# EEZ_CF-DIC_r4B4.net
KiCad netlist of a schematic drawn in EAGLE
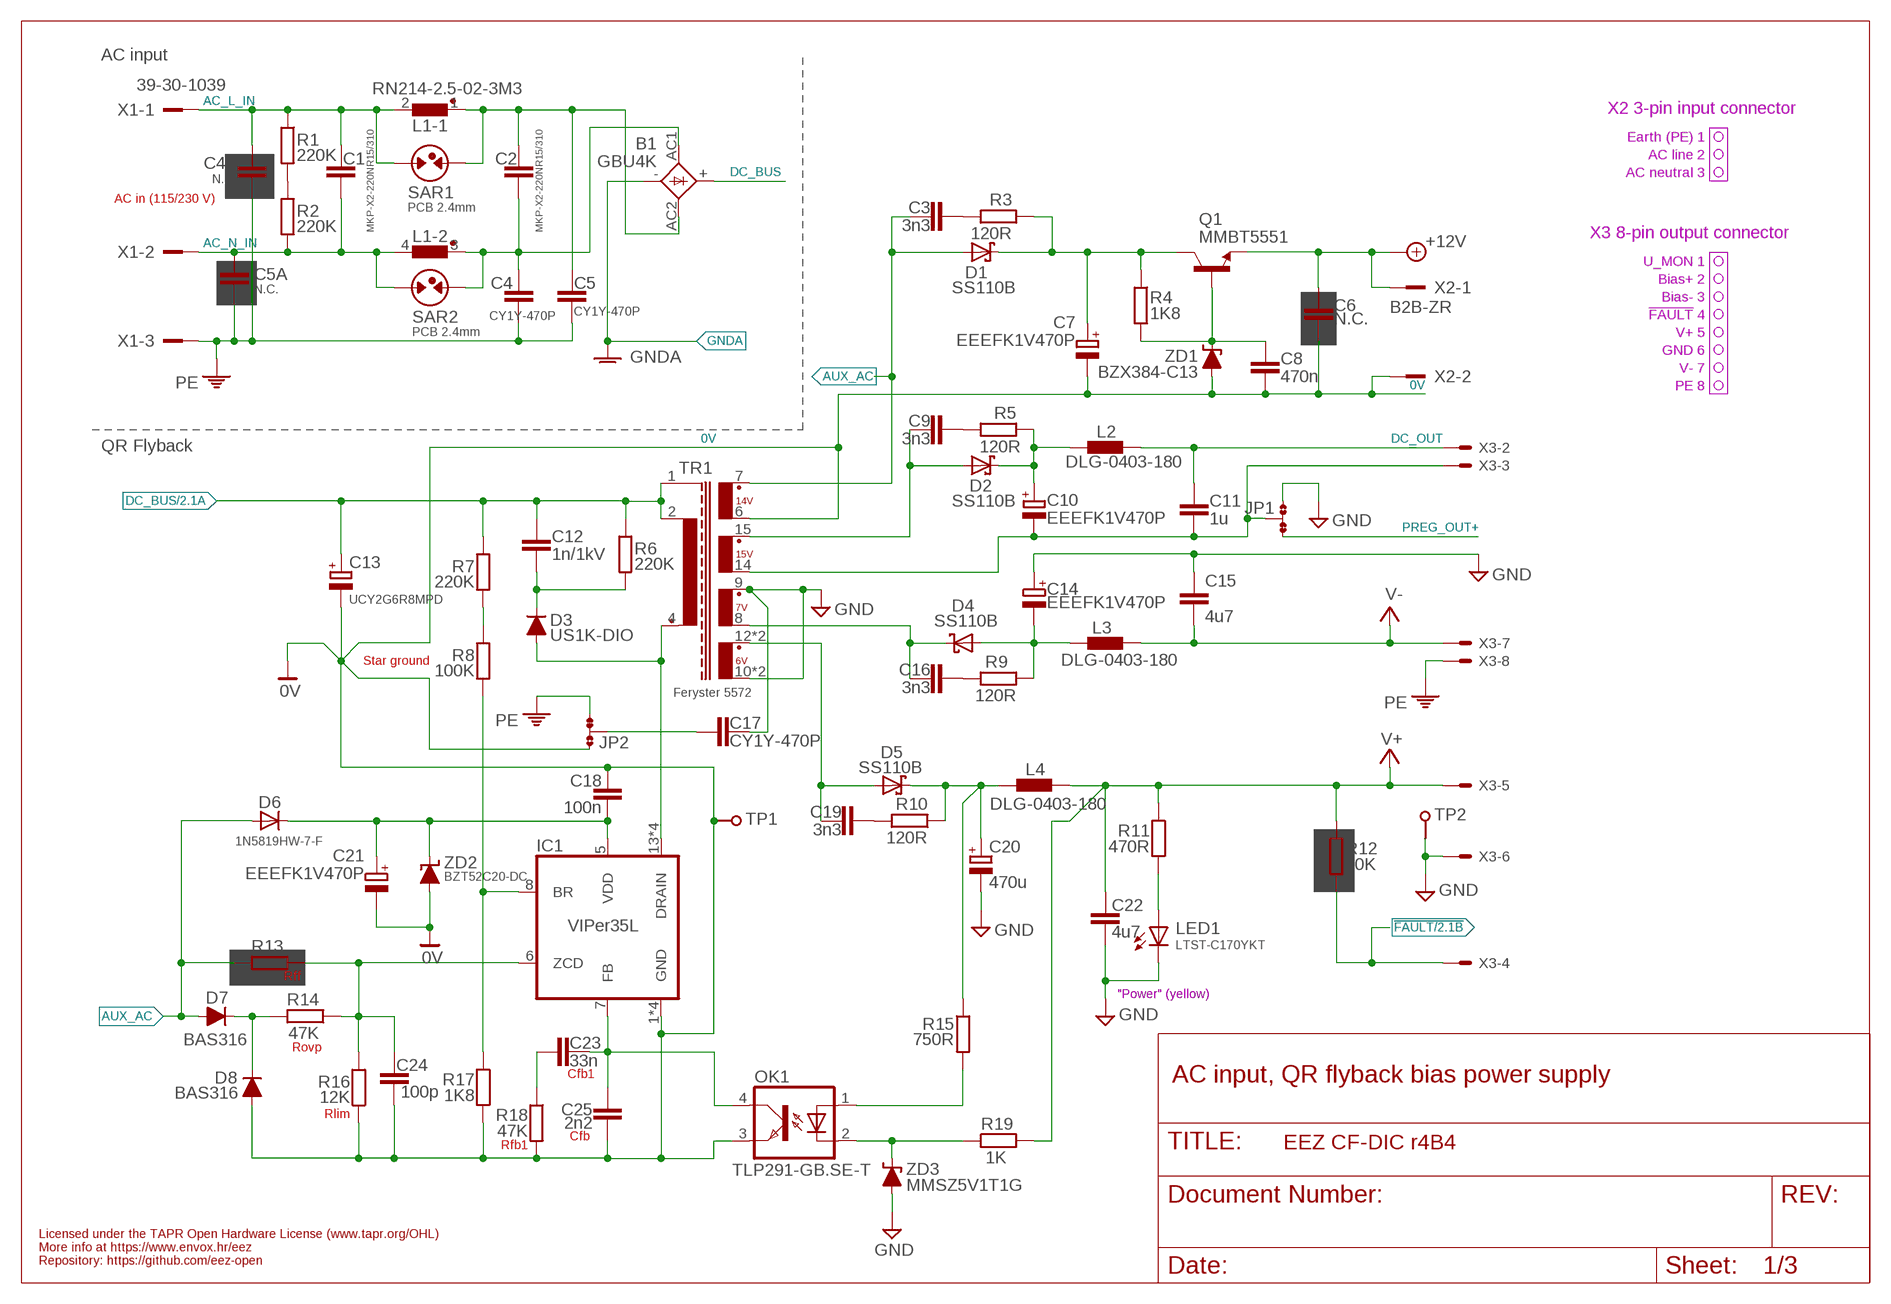
[diagram p0: schematic, sheet 1]
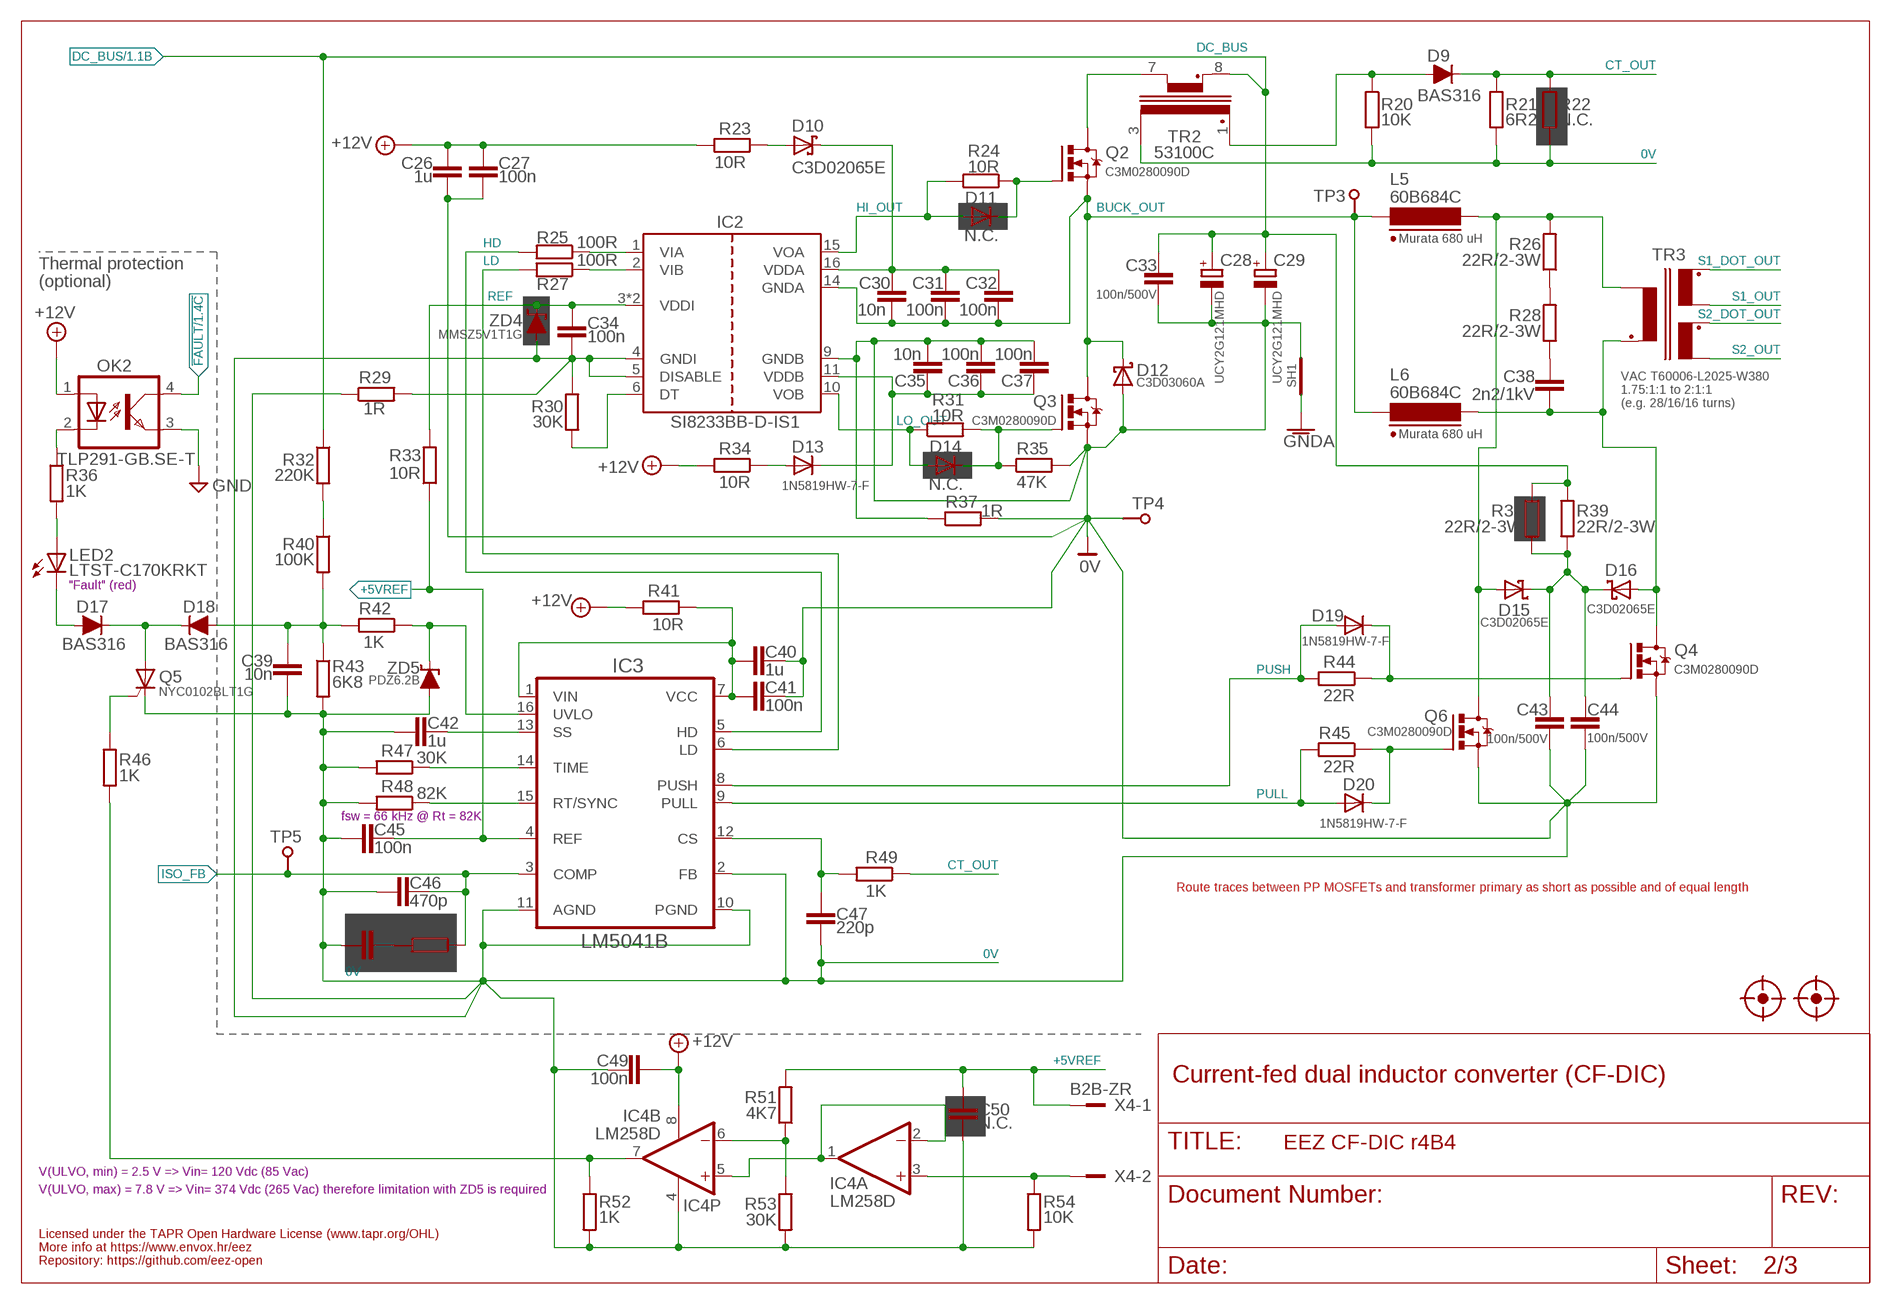
[diagram p1: schematic, sheet 2]
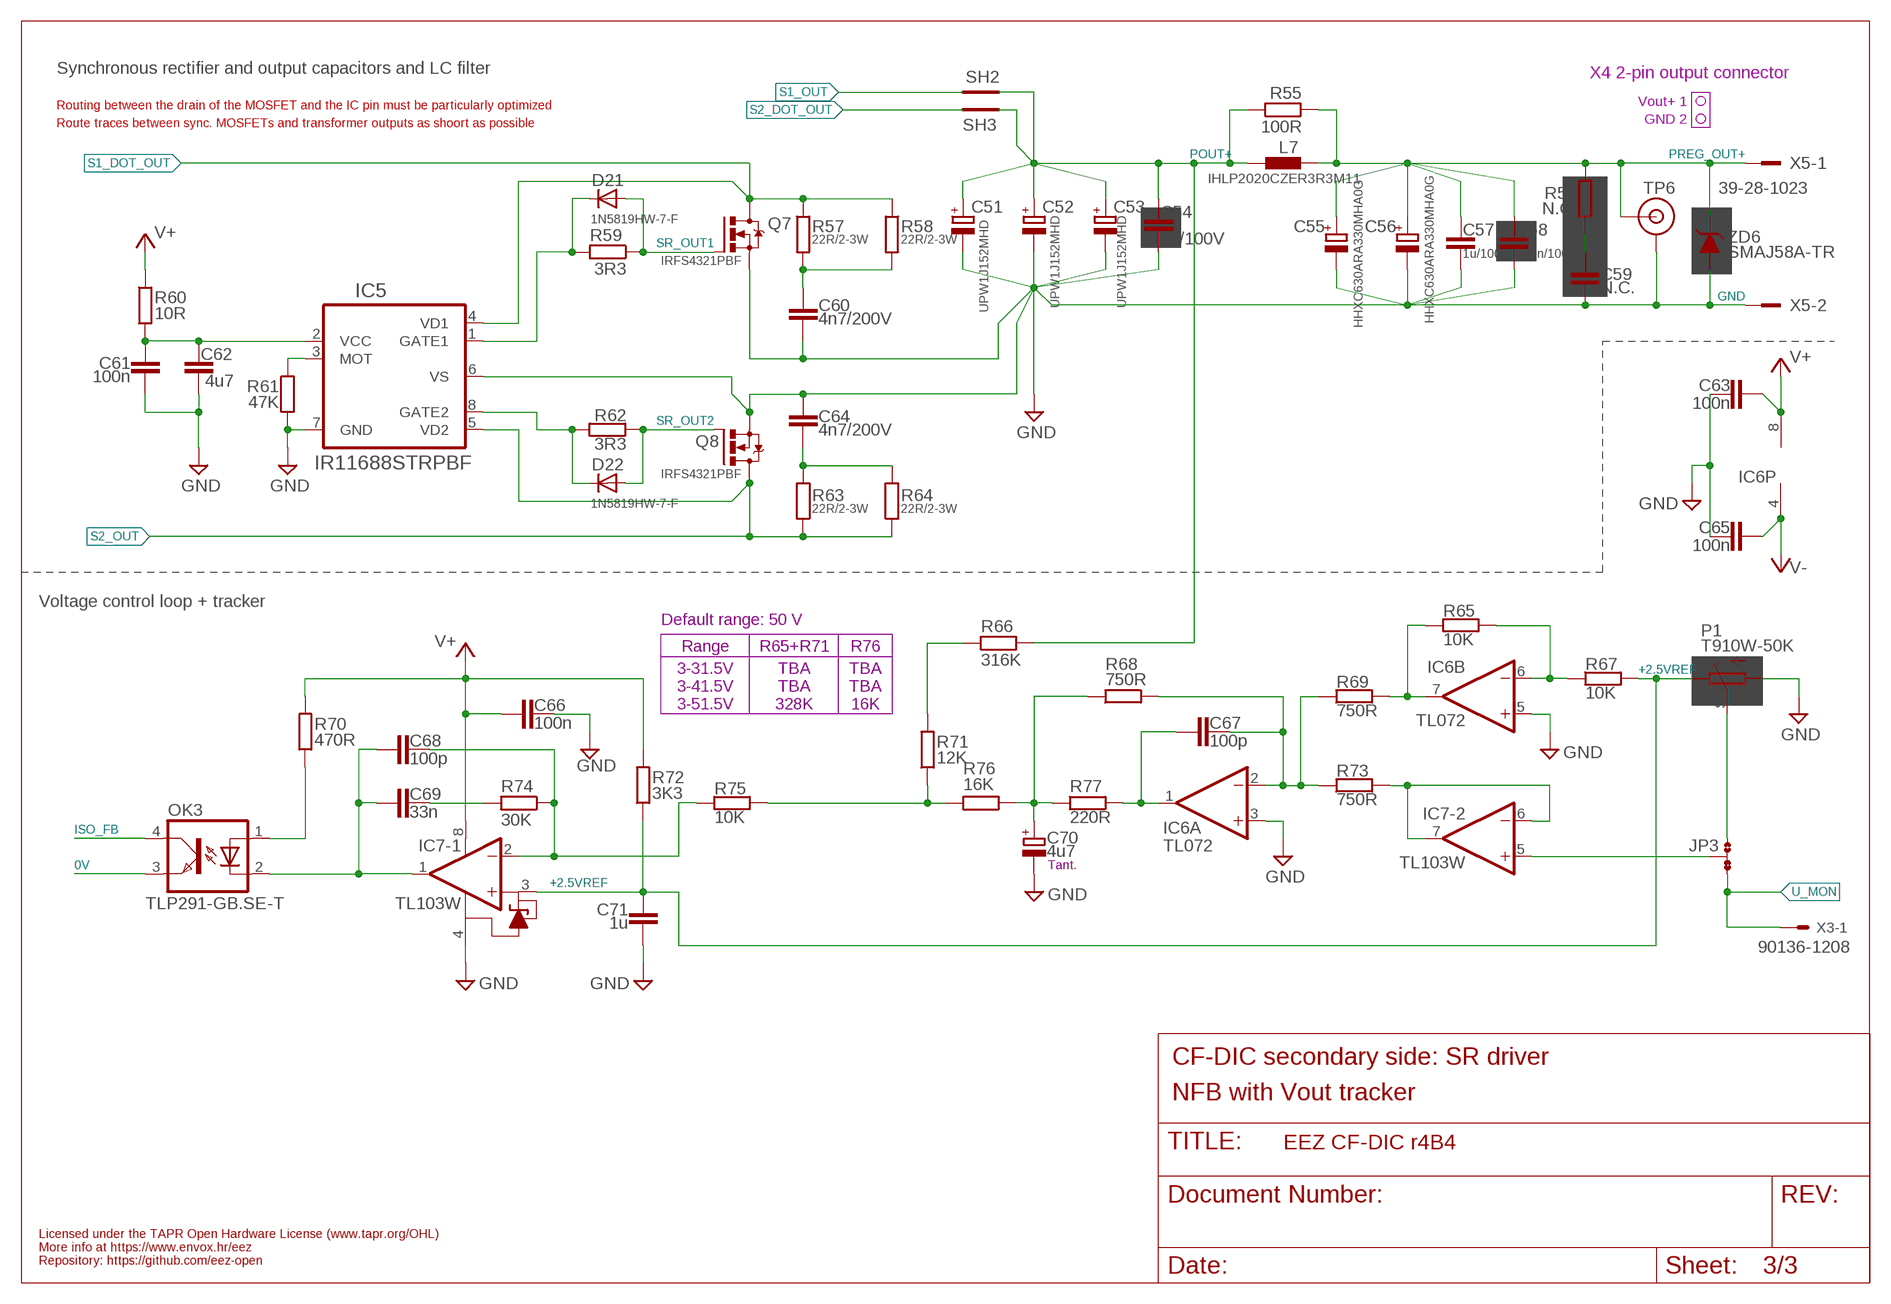
[diagram p2: schematic, sheet 3]

(export (version "E")
  (design (tool "Eeschema 10.0.6"))
  (components
    (comp (ref "C51")
      (value "UPW1J152MHD")
      (footprint "eagle-import:ECAP7.5_18")
      (libsource (lib "eagle-import") (part "ECAP7.5G_18MM"))
    )
    (comp (ref "C52")
      (value "UPW1J152MHD")
      (footprint "eagle-import:ECAP7.5_18")
      (libsource (lib "eagle-import") (part "ECAP7.5G_18MM"))
    )
    (comp (ref "C53")
      (value "UPW1J152MHD")
      (footprint "eagle-import:ECAP7.5_18")
      (libsource (lib "eagle-import") (part "ECAP7.5G_18MM"))
    )
    (comp (ref "C54")
      (value "1u/100V")
      (footprint "eagle-import:C1206")
      (libsource (lib "eagle-import") (part "C-EUC1206"))
    )
    (comp (ref "C55")
      (value "HHXC630ARA330MHA0G ")
      (footprint "eagle-import:CAPAE830X1050N")
      (fields
        (field (name "MPN") "EEE-FK1J470P")
        (field (name "TOLERANCE") "±20 %")
        (field (name "MPN_1") "EEE-FK1J470P")
        (field (name "OC_FARNELL") "9696032  ")
        (field (name "OC_NEWARK") "96K9403")
        (field (name "PACKAGE") "CASE-F")
        (field (name "SUPPLIER") "PANASONIC")
        (field (name "TOLERANCE_1") "±20 %")
        (field (name "VOLTAGERATING") "63 V")
      )
      (libsource (lib "eagle-import") (part "EEE--CASE-FFK1J470P"))
    )
    (comp (ref "C56")
      (value "HHXC630ARA330MHA0G")
      (footprint "eagle-import:CAPAE830X1050N")
      (fields (field (name "MPN") "EEE-FK1J470P") (field (name "TOLERANCE") "±20 %"))
      (libsource (lib "eagle-import") (part "EEE--CASE-FFK1J470P"))
    )
    (comp (ref "C57")
      (value "1u/100V")
      (footprint "eagle-import:C1206")
      (libsource (lib "eagle-import") (part "C-EUC1206"))
    )
    (comp (ref "C58")
      (value "100n/100V")
      (footprint "eagle-import:C0805")
      (libsource (lib "eagle-import") (part "C-EUC0805"))
    )
    (comp (ref "C59")
      (value "N.C.")
      (footprint "eagle-import:C1206")
      (libsource (lib "eagle-import") (part "C-EUC1206"))
    )
    (comp (ref "C60")
      (value "4n7/200V")
      (footprint "eagle-import:C1206")
      (libsource (lib "eagle-import") (part "C-EUC1206"))
    )
    (comp (ref "C61")
      (value "100n")
      (footprint "eagle-import:C0603")
      (libsource (lib "eagle-import") (part "C-EUC0603"))
    )
    (comp (ref "C62")
      (value "4u7")
      (footprint "eagle-import:C1206")
      (libsource (lib "eagle-import") (part "C-EUC1206"))
    )
    (comp (ref "C63")
      (value "100n")
      (footprint "eagle-import:C0603")
      (libsource (lib "eagle-import") (part "C-EUC0603"))
    )
    (comp (ref "C64")
      (value "4n7/200V")
      (footprint "eagle-import:C1206")
      (libsource (lib "eagle-import") (part "C-EUC1206"))
    )
    (comp (ref "C65")
      (value "100n")
      (footprint "eagle-import:C0603")
      (libsource (lib "eagle-import") (part "C-EUC0603"))
    )
    (comp (ref "C66")
      (value "100n")
      (footprint "eagle-import:C0603")
      (libsource (lib "eagle-import") (part "C-EUC0603"))
    )
    (comp (ref "C67")
      (value "100p")
      (footprint "eagle-import:C0805")
      (libsource (lib "eagle-import") (part "C-EUC0805"))
    )
    (comp (ref "C68")
      (value "100p")
      (footprint "eagle-import:C0805")
      (libsource (lib "eagle-import") (part "C-EUC0805"))
    )
    (comp (ref "C69")
      (value "33n")
      (footprint "eagle-import:C0805")
      (libsource (lib "eagle-import") (part "C-EUC0805"))
    )
    (comp (ref "C70")
      (value "4u7")
      (footprint "eagle-import:EC1206")
      (libsource (lib "eagle-import") (part "ECAP1206"))
    )
    (comp (ref "C71")
      (value "1u")
      (footprint "eagle-import:C0805")
      (libsource (lib "eagle-import") (part "C-EUC0805"))
    )
    (comp (ref "D21")
      (value "1N5819HW-7-F")
      (footprint "eagle-import:SOD323-W")
      (libsource (lib "eagle-import") (part "DIODE-SOD323-W"))
    )
    (comp (ref "D22")
      (value "1N5819HW-7-F")
      (footprint "eagle-import:SOD323-W")
      (libsource (lib "eagle-import") (part "DIODE-SOD323-W"))
    )
    (comp (ref "IC5")
      (value "IR11688STRPBF")
      (footprint "eagle-import:SO8")
      (libsource (lib "eagle-import") (part "IR11688"))
    )
    (comp (ref "IC6")
      (value "TL072")
      (footprint "eagle-import:SOIC127P600X173-8N")
      (libsource (lib "eagle-import") (part "TL072SOIC8"))
    )
    (comp (ref "IC7")
      (value "TL103W")
      (footprint "eagle-import:SOIC127P600X173-8N")
      (libsource (lib "eagle-import") (part "TL103W"))
    )
    (comp (ref "JP3")
      (value "JP3-CUT")
      (footprint "eagle-import:JP3-CUT")
      (libsource (lib "eagle-import") (part "JP3-CUT"))
    )
    (comp (ref "L7")
      (value "IHLP2020CZER3R3M11")
      (footprint "eagle-import:IHLP-2020BZ-11")
      (libsource (lib "eagle-import") (part "EEZ_inductors_and_transformers_IHLP-2020BZ-11"))
    )
    (comp (ref "OK3")
      (value "TLP291-GB.SE-T")
      (footprint "eagle-import:SO4")
      (libsource (lib "eagle-import") (part "TLP291"))
    )
    (comp (ref "P1")
      (value "T910W-50K")
      (footprint "eagle-import:S64W")
      (libsource (lib "eagle-import") (part "TPOT-S64W"))
    )
    (comp (ref "Q7")
      (value "IRFS4321PBF")
      (footprint "eagle-import:TO263")
      (libsource (lib "eagle-import") (part "N-MOSFETTO263"))
    )
    (comp (ref "Q8")
      (value "IRFS4321PBF")
      (footprint "eagle-import:TO263")
      (libsource (lib "eagle-import") (part "N-MOSFETTO263"))
    )
    (comp (ref "R55")
      (value "100R")
      (footprint "eagle-import:R0805")
      (libsource (lib "eagle-import") (part "R-EU_R0805"))
    )
    (comp (ref "R56")
      (value "N.C.")
      (footprint "eagle-import:R1210")
      (libsource (lib "eagle-import") (part "R-EU_R1210"))
    )
    (comp (ref "R57")
      (value "22R/2-3W")
      (footprint "eagle-import:R2512")
      (libsource (lib "eagle-import") (part "R-EU_R2512"))
    )
    (comp (ref "R58")
      (value "22R/2-3W")
      (footprint "eagle-import:R2512")
      (libsource (lib "eagle-import") (part "R-EU_R2512"))
    )
    (comp (ref "R59")
      (value "3R3")
      (footprint "eagle-import:R0805")
      (libsource (lib "eagle-import") (part "R-EU_R0805"))
    )
    (comp (ref "R60")
      (value "10R")
      (footprint "eagle-import:R0805")
      (libsource (lib "eagle-import") (part "R-EU_R0805"))
    )
    (comp (ref "R61")
      (value "47K")
      (footprint "eagle-import:R0805")
      (libsource (lib "eagle-import") (part "R-EU_R0805"))
    )
    (comp (ref "R62")
      (value "3R3")
      (footprint "eagle-import:R0805")
      (libsource (lib "eagle-import") (part "R-EU_R0805"))
    )
    (comp (ref "R63")
      (value "22R/2-3W")
      (footprint "eagle-import:R2512")
      (libsource (lib "eagle-import") (part "R-EU_R2512"))
    )
    (comp (ref "R64")
      (value "22R/2-3W")
      (footprint "eagle-import:R2512")
      (libsource (lib "eagle-import") (part "R-EU_R2512"))
    )
    (comp (ref "R65")
      (value "10K")
      (footprint "eagle-import:R0805")
      (libsource (lib "eagle-import") (part "R-EU_R0805"))
    )
    (comp (ref "R66")
      (value "316K")
      (footprint "eagle-import:R0805")
      (libsource (lib "eagle-import") (part "R-EU_R0805"))
    )
    (comp (ref "R67")
      (value "10K")
      (footprint "eagle-import:R0805")
      (libsource (lib "eagle-import") (part "R-EU_R0805"))
    )
    (comp (ref "R68")
      (value "750R")
      (footprint "eagle-import:R0805")
      (libsource (lib "eagle-import") (part "R-EU_R0805"))
    )
    (comp (ref "R69")
      (value "750R")
      (footprint "eagle-import:R0805")
      (libsource (lib "eagle-import") (part "R-EU_R0805"))
    )
    (comp (ref "R70")
      (value "470R")
      (footprint "eagle-import:R0805")
      (libsource (lib "eagle-import") (part "R-EU_R0805"))
    )
    (comp (ref "R71")
      (value "12K")
      (footprint "eagle-import:R0805")
      (libsource (lib "eagle-import") (part "R-EU_R0805"))
    )
    (comp (ref "R72")
      (value "3K3")
      (footprint "eagle-import:R0805")
      (libsource (lib "eagle-import") (part "R-EU_R0805"))
    )
    (comp (ref "R73")
      (value "750R")
      (footprint "eagle-import:R0805")
      (libsource (lib "eagle-import") (part "R-EU_R0805"))
    )
    (comp (ref "R74")
      (value "30K")
      (footprint "eagle-import:R0805")
      (libsource (lib "eagle-import") (part "R-EU_R0805"))
    )
    (comp (ref "R75")
      (value "10K")
      (footprint "eagle-import:R0805")
      (libsource (lib "eagle-import") (part "R-EU_R0805"))
    )
    (comp (ref "R76")
      (value "16K")
      (footprint "eagle-import:R0805")
      (libsource (lib "eagle-import") (part "R-EU_R0805"))
    )
    (comp (ref "R77")
      (value "220R")
      (footprint "eagle-import:R0805")
      (libsource (lib "eagle-import") (part "R-EU_R0805"))
    )
    (comp (ref "SH2")
      (value "SHORTNOHOLE")
      (footprint "eagle-import:SHORT_NOHOLE")
      (libsource (lib "eagle-import") (part "SHORTNOHOLE"))
    )
    (comp (ref "SH3")
      (value "SHORTNOHOLE")
      (footprint "eagle-import:SHORT_NOHOLE")
      (libsource (lib "eagle-import") (part "SHORTNOHOLE"))
    )
    (comp (ref "TP6")
      (value "TEST_POINT-2")
      (footprint "eagle-import:TP_1.1MM_2")
      (libsource (lib "eagle-import") (part "TEST_POINT-2"))
    )
    (comp (ref "X3")
      (value "90136-1208")
      (footprint "eagle-import:70543-08")
      (libsource (lib "eagle-import") (part "C-GRID-08-70543"))
    )
    (comp (ref "X5")
      (value "39-28-1023")
      (footprint "eagle-import:MINIFIT_5566-02A")
      (libsource (lib "eagle-import") (part "MINIFIT_5566-02A"))
    )
    (comp (ref "ZD6")
      (value "SMAJ58A-TR")
      (footprint "eagle-import:DO214AC")
      (libsource (lib "eagle-import") (part "PSMAXX"))
    )
    (comp (ref "B1")
      (value "GBU4K")
      (footprint "eagle-import:GBU4K_CRE")
      (libsource (lib "eagle-import") (part "BRIDGE-CREEPAGE"))
    )
    (comp (ref "C1")
      (value "MKP-X2-220NR15/310")
      (footprint "eagle-import:C150-072X183")
      (libsource (lib "eagle-import") (part "C-EU150-072X183"))
    )
    (comp (ref "C2")
      (value "MKP-X2-220NR15/310")
      (footprint "eagle-import:C150-072X183")
      (libsource (lib "eagle-import") (part "C-EU150-072X183"))
    )
    (comp (ref "C3")
      (value "3n3")
      (footprint "eagle-import:C0805")
      (libsource (lib "eagle-import") (part "C-EUC0805"))
    )
    (comp (ref "C4")
      (value "CY1Y-470P")
      (footprint "eagle-import:CY075-032X103")
      (libsource (lib "eagle-import") (part "C-EUCY"))
    )
    (comp (ref "C4A")
      (value "N.C.")
      (footprint "eagle-import:CY075-032X103")
      (libsource (lib "eagle-import") (part "C-EUCY"))
    )
    (comp (ref "C5")
      (value "CY1Y-470P")
      (footprint "eagle-import:CY075-032X103")
      (libsource (lib "eagle-import") (part "C-EUCY"))
    )
    (comp (ref "C5A")
      (value "N.C.")
      (footprint "eagle-import:CY075-032X103")
      (libsource (lib "eagle-import") (part "C-EUCY"))
    )
    (comp (ref "C6")
      (value "N.C.")
      (footprint "eagle-import:C0603")
      (libsource (lib "eagle-import") (part "C-EUC0603"))
    )
    (comp (ref "C7")
      (value "EEEFK1V470P")
      (footprint "eagle-import:CAPAE660X610N")
      (libsource (lib "eagle-import") (part "ECAPPANASONIC_H"))
    )
    (comp (ref "C8")
      (value "470n")
      (footprint "eagle-import:C0805")
      (libsource (lib "eagle-import") (part "C-EUC0805"))
    )
    (comp (ref "C9")
      (value "3n3")
      (footprint "eagle-import:C0805")
      (libsource (lib "eagle-import") (part "C-EUC0805"))
    )
    (comp (ref "C10")
      (value "EEEFK1V470P")
      (footprint "eagle-import:CAPAE660X610N")
      (libsource (lib "eagle-import") (part "ECAPPANASONIC_H"))
    )
    (comp (ref "C11")
      (value "1u")
      (footprint "eagle-import:C0805")
      (libsource (lib "eagle-import") (part "C-EUC0805"))
    )
    (comp (ref "C12")
      (value "1n/1kV")
      (footprint "eagle-import:C1210")
      (libsource (lib "eagle-import") (part "C-EUC1210"))
    )
    (comp (ref "C13")
      (value "UCY2G6R8MPD")
      (footprint "eagle-import:ECAP5_10.5")
      (libsource (lib "eagle-import") (part "ECAP5G_10.5MM"))
    )
    (comp (ref "C14")
      (value "EEEFK1V470P")
      (footprint "eagle-import:CAPAE660X610N")
      (libsource (lib "eagle-import") (part "ECAPPANASONIC_H"))
    )
    (comp (ref "C15")
      (value "4u7")
      (footprint "eagle-import:C1206")
      (libsource (lib "eagle-import") (part "C-EUC1206"))
    )
    (comp (ref "C16")
      (value "3n3")
      (footprint "eagle-import:C0805")
      (libsource (lib "eagle-import") (part "C-EUC0805"))
    )
    (comp (ref "C17")
      (value "CY1Y-470P")
      (footprint "eagle-import:CY075-032X103")
      (libsource (lib "eagle-import") (part "C-EUCY"))
    )
    (comp (ref "C18")
      (value "100n")
      (footprint "eagle-import:C0603")
      (libsource (lib "eagle-import") (part "C-EUC0603"))
    )
    (comp (ref "C19")
      (value "3n3")
      (footprint "eagle-import:C0805")
      (libsource (lib "eagle-import") (part "C-EUC0805"))
    )
    (comp (ref "C20")
      (value "470u")
      (footprint "eagle-import:ECAP5_10.5")
      (libsource (lib "eagle-import") (part "ECAP5G_10.5MM"))
    )
    (comp (ref "C21")
      (value "EEEFK1V470P")
      (footprint "eagle-import:CAPAE660X610N")
      (libsource (lib "eagle-import") (part "ECAPPANASONIC_H"))
    )
    (comp (ref "C22")
      (value "4u7")
      (footprint "eagle-import:C1206")
      (libsource (lib "eagle-import") (part "C-EUC1206"))
    )
    (comp (ref "C23")
      (value "33n")
      (footprint "eagle-import:C0805")
      (libsource (lib "eagle-import") (part "C-EUC0805"))
    )
    (comp (ref "C24")
      (value "100p")
      (footprint "eagle-import:C0805")
      (libsource (lib "eagle-import") (part "C-EUC0805"))
    )
    (comp (ref "C25")
      (value "2n2")
      (footprint "eagle-import:C0805")
      (libsource (lib "eagle-import") (part "C-EUC0805"))
    )
    (comp (ref "D1")
      (value "SS110B")
      (footprint "eagle-import:SMB")
      (libsource (lib "eagle-import") (part "SCHOTTKYSMB"))
    )
    (comp (ref "D2")
      (value "SS110B")
      (footprint "eagle-import:SMB")
      (libsource (lib "eagle-import") (part "SCHOTTKYSMB"))
    )
    (comp (ref "D3")
      (value "US1K-DIO")
      (footprint "eagle-import:DO214AA")
      (libsource (lib "eagle-import") (part "DIODEDO214AA"))
    )
    (comp (ref "D4")
      (value "SS110B")
      (footprint "eagle-import:SMB")
      (libsource (lib "eagle-import") (part "SCHOTTKYSMB"))
    )
    (comp (ref "D5")
      (value "SS110B")
      (footprint "eagle-import:SMB")
      (libsource (lib "eagle-import") (part "SCHOTTKYSMB"))
    )
    (comp (ref "D6")
      (value "1N5819HW-7-F")
      (footprint "eagle-import:SOD323-W")
      (libsource (lib "eagle-import") (part "DIODE-SOD323-W"))
    )
    (comp (ref "D7")
      (value "BAS316")
      (footprint "eagle-import:SOD323-R")
      (libsource (lib "eagle-import") (part "DIODESOD323R"))
    )
    (comp (ref "D8")
      (value "BAS316")
      (footprint "eagle-import:SOD323-R")
      (libsource (lib "eagle-import") (part "DIODESOD323R"))
    )
    (comp (ref "IC1")
      (value "VIPer35L")
      (footprint "eagle-import:SOIC-16")
      (libsource (lib "eagle-import") (part "VIPER35"))
    )
    (comp (ref "JP1")
      (value "JP3-CUT")
      (footprint "eagle-import:JP3-CUT")
      (libsource (lib "eagle-import") (part "JP3-CUT"))
    )
    (comp (ref "JP2")
      (value "JP3-CUT")
      (footprint "eagle-import:JP3-CUT")
      (libsource (lib "eagle-import") (part "JP3-CUT"))
    )
    (comp (ref "L1")
      (value "RN214-2.5-02-3M3")
      (footprint "eagle-import:RN214")
      (fields (field (name "FARNELL") "1191518"))
      (libsource (lib "eagle-import") (part "EEZ_inductors_and_transformers_RN214"))
    )
    (comp (ref "L2")
      (value "DLG-0403-180")
      (footprint "eagle-import:DE0403")
      (libsource (lib "eagle-import") (part "EEZ_inductors_and_transformers_DE0403"))
    )
    (comp (ref "L3")
      (value "DLG-0403-180")
      (footprint "eagle-import:DE0403")
      (libsource (lib "eagle-import") (part "EEZ_inductors_and_transformers_DE0403"))
    )
    (comp (ref "L4")
      (value "DLG-0403-180")
      (footprint "eagle-import:DE0403")
      (libsource (lib "eagle-import") (part "EEZ_inductors_and_transformers_DE0403"))
    )
    (comp (ref "LED1")
      (value "LTST-C170YKT")
      (footprint "eagle-import:LED_0805")
      (libsource (lib "eagle-import") (part "LED0805"))
    )
    (comp (ref "OK1")
      (value "TLP291-GB.SE-T")
      (footprint "eagle-import:SO4")
      (libsource (lib "eagle-import") (part "TLP291"))
    )
    (comp (ref "Q1")
      (value "MMBT5551")
      (footprint "eagle-import:SOT23-BEC")
      (libsource (lib "eagle-import") (part "-NPN-SOT23-BECMMBT5551LT1"))
    )
    (comp (ref "R1")
      (value "220K")
      (footprint "eagle-import:R1206")
      (libsource (lib "eagle-import") (part "R-EU_R1206"))
    )
    (comp (ref "R2")
      (value "220K")
      (footprint "eagle-import:R1206")
      (libsource (lib "eagle-import") (part "R-EU_R1206"))
    )
    (comp (ref "R3")
      (value "120R")
      (footprint "eagle-import:R0805")
      (libsource (lib "eagle-import") (part "R-EU_R0805"))
    )
    (comp (ref "R4")
      (value "1K8")
      (footprint "eagle-import:R0805")
      (libsource (lib "eagle-import") (part "R-EU_R0805"))
    )
    (comp (ref "R5")
      (value "120R")
      (footprint "eagle-import:R0805")
      (libsource (lib "eagle-import") (part "R-EU_R0805"))
    )
    (comp (ref "R6")
      (value "220K")
      (footprint "eagle-import:R1206")
      (libsource (lib "eagle-import") (part "R-EU_R1206"))
    )
    (comp (ref "R7")
      (value "220K")
      (footprint "eagle-import:R1206")
      (libsource (lib "eagle-import") (part "R-EU_R1206"))
    )
    (comp (ref "R8")
      (value "100K")
      (footprint "eagle-import:R0805")
      (libsource (lib "eagle-import") (part "R-EU_R0805"))
    )
    (comp (ref "R9")
      (value "120R")
      (footprint "eagle-import:R0805")
      (libsource (lib "eagle-import") (part "R-EU_R0805"))
    )
    (comp (ref "R10")
      (value "120R")
      (footprint "eagle-import:R0805")
      (libsource (lib "eagle-import") (part "R-EU_R0805"))
    )
    (comp (ref "R11")
      (value "470R")
      (footprint "eagle-import:R0805")
      (libsource (lib "eagle-import") (part "R-EU_R0805"))
    )
    (comp (ref "R12")
      (value "10K")
      (footprint "eagle-import:R0805")
      (libsource (lib "eagle-import") (part "R-EU_R0805"))
    )
    (comp (ref "R13")
      (value "N.C.")
      (footprint "eagle-import:R0805")
      (libsource (lib "eagle-import") (part "R-EU_R0805"))
    )
    (comp (ref "R14")
      (value "47K")
      (footprint "eagle-import:R0805")
      (libsource (lib "eagle-import") (part "R-EU_R0805"))
    )
    (comp (ref "R15")
      (value "750R")
      (footprint "eagle-import:R0805")
      (libsource (lib "eagle-import") (part "R-EU_R0805"))
    )
    (comp (ref "R16")
      (value "12K")
      (footprint "eagle-import:R0805")
      (libsource (lib "eagle-import") (part "R-EU_R0805"))
    )
    (comp (ref "R17")
      (value "1K8")
      (footprint "eagle-import:R0805")
      (libsource (lib "eagle-import") (part "R-EU_R0805"))
    )
    (comp (ref "R18")
      (value "47K")
      (footprint "eagle-import:R0805")
      (libsource (lib "eagle-import") (part "R-EU_R0805"))
    )
    (comp (ref "R19")
      (value "1K")
      (footprint "eagle-import:R0805")
      (libsource (lib "eagle-import") (part "R-EU_R0805"))
    )
    (comp (ref "SAR1")
      (value "PCB 2.4mm")
      (footprint "eagle-import:PCB-SAR_2.4MM")
      (libsource (lib "eagle-import") (part "SARPCB-2.4MM"))
    )
    (comp (ref "SAR2")
      (value "PCB 2.4mm")
      (footprint "eagle-import:PCB-SAR_2.4MM")
      (libsource (lib "eagle-import") (part "SARPCB-2.4MM"))
    )
    (comp (ref "TP1")
      (value "PCB_TEST_TABSHIELD")
      (footprint "eagle-import:PCB_SHIELD_TAB")
      (libsource (lib "eagle-import") (part "PCB_TEST_TABSHIELD"))
    )
    (comp (ref "TP2")
      (value "PCB_TEST_TABSHIELD")
      (footprint "eagle-import:PCB_SHIELD_TAB")
      (libsource (lib "eagle-import") (part "PCB_TEST_TABSHIELD"))
    )
    (comp (ref "TR1")
      (value "Feryster 5572")
      (footprint "eagle-import:FERYSTER_5572")
      (libsource (lib "eagle-import") (part "EEZ_inductors_and_transformers_FERYSTER_5572"))
    )
    (comp (ref "X1")
      (value "39-30-1039")
      (footprint "eagle-import:MINIFIT_39301039_CRE")
      (libsource (lib "eagle-import") (part "MINIFIT_39301039-CREEPAGE"))
    )
    (comp (ref "X2")
      (value "B2B-ZR")
      (footprint "eagle-import:B2B-ZR")
      (libsource (lib "eagle-import") (part "B2B-ZR"))
    )
    (comp (ref "ZD1")
      (value "BZX384-C13")
      (footprint "eagle-import:SOD323-W")
      (libsource (lib "eagle-import") (part "ZENER-DIODESOD323"))
    )
    (comp (ref "ZD2")
      (value "BZT52C20-DC")
      (footprint "eagle-import:SOD123")
      (libsource (lib "eagle-import") (part "ZENER-DIODESOD123"))
    )
    (comp (ref "ZD3")
      (value "MMSZ5V1T1G")
      (footprint "eagle-import:SOD323-W")
      (libsource (lib "eagle-import") (part "ZENER-DIODESOD323"))
    )
    (comp (ref "C26")
      (value "1u")
      (footprint "eagle-import:C0805")
      (libsource (lib "eagle-import") (part "C-EUC0805"))
    )
    (comp (ref "C27")
      (value "100n")
      (footprint "eagle-import:C0603")
      (libsource (lib "eagle-import") (part "C-EUC0603"))
    )
    (comp (ref "C28")
      (value "UCY2G121MHD")
      (footprint "eagle-import:ECAP7.5_18")
      (libsource (lib "eagle-import") (part "ECAP7.5G_18MM"))
    )
    (comp (ref "C29")
      (value "UCY2G121MHD")
      (footprint "eagle-import:ECAP7.5_18")
      (libsource (lib "eagle-import") (part "ECAP7.5G_18MM"))
    )
    (comp (ref "C30")
      (value "10n")
      (footprint "eagle-import:C0603")
      (libsource (lib "eagle-import") (part "C-EUC0603"))
    )
    (comp (ref "C31")
      (value "100n")
      (footprint "eagle-import:C0603")
      (libsource (lib "eagle-import") (part "C-EUC0603"))
    )
    (comp (ref "C32")
      (value "100n")
      (footprint "eagle-import:C0603")
      (libsource (lib "eagle-import") (part "C-EUC0603"))
    )
    (comp (ref "C33")
      (value "100n/500V")
      (footprint "eagle-import:C1812")
      (libsource (lib "eagle-import") (part "C-EUC1812"))
    )
    (comp (ref "C34")
      (value "100n")
      (footprint "eagle-import:C0603")
      (libsource (lib "eagle-import") (part "C-EUC0603"))
    )
    (comp (ref "C35")
      (value "10n")
      (footprint "eagle-import:C0603")
      (libsource (lib "eagle-import") (part "C-EUC0603"))
    )
    (comp (ref "C36")
      (value "100n")
      (footprint "eagle-import:C0603")
      (libsource (lib "eagle-import") (part "C-EUC0603"))
    )
    (comp (ref "C37")
      (value "100n")
      (footprint "eagle-import:C0603")
      (libsource (lib "eagle-import") (part "C-EUC0603"))
    )
    (comp (ref "C38")
      (value "2n2/1kV")
      (footprint "eagle-import:C1210")
      (libsource (lib "eagle-import") (part "C-EUC1210"))
    )
    (comp (ref "C39")
      (value "10n")
      (footprint "eagle-import:C0603")
      (libsource (lib "eagle-import") (part "C-EUC0603"))
    )
    (comp (ref "C40")
      (value "1u")
      (footprint "eagle-import:C0805")
      (libsource (lib "eagle-import") (part "C-EUC0805"))
    )
    (comp (ref "C41")
      (value "100n")
      (footprint "eagle-import:C0603")
      (libsource (lib "eagle-import") (part "C-EUC0603"))
    )
    (comp (ref "C42")
      (value "1u")
      (footprint "eagle-import:C0805")
      (libsource (lib "eagle-import") (part "C-EUC0805"))
    )
    (comp (ref "C43")
      (value "100n/500V")
      (footprint "eagle-import:C1812")
      (libsource (lib "eagle-import") (part "C-EUC1812"))
    )
    (comp (ref "C44")
      (value "100n/500V")
      (footprint "eagle-import:C1812")
      (libsource (lib "eagle-import") (part "C-EUC1812"))
    )
    (comp (ref "C45")
      (value "100n")
      (footprint "eagle-import:C0603")
      (libsource (lib "eagle-import") (part "C-EUC0603"))
    )
    (comp (ref "C46")
      (value "470p")
      (footprint "eagle-import:C0805")
      (libsource (lib "eagle-import") (part "C-EUC0805"))
    )
    (comp (ref "C47")
      (value "220p")
      (footprint "eagle-import:C0805")
      (libsource (lib "eagle-import") (part "C-EUC0805"))
    )
    (comp (ref "C48")
      (value "N.C.")
      (footprint "eagle-import:C0805")
      (libsource (lib "eagle-import") (part "C-EUC0805"))
    )
    (comp (ref "C49")
      (value "100n")
      (footprint "eagle-import:C0603")
      (libsource (lib "eagle-import") (part "C-EUC0603"))
    )
    (comp (ref "C50")
      (value "N.C.")
      (footprint "eagle-import:C0603")
      (libsource (lib "eagle-import") (part "C-EUC0603"))
    )
    (comp (ref "D9")
      (value "BAS316")
      (footprint "eagle-import:SOD323-R")
      (libsource (lib "eagle-import") (part "DIODESOD323R"))
    )
    (comp (ref "D10")
      (value "C3D02065E")
      (footprint "eagle-import:TO252")
      (libsource (lib "eagle-import") (part "SCHOTTKY-SIC"))
    )
    (comp (ref "D11")
      (value "N.C.")
      (footprint "eagle-import:SOD323-W")
      (libsource (lib "eagle-import") (part "DIODE-SOD323-W"))
    )
    (comp (ref "D12")
      (value "C3D03060A")
      (footprint "eagle-import:TO220-2")
      (libsource (lib "eagle-import") (part "SCHOTTKY-TO220"))
    )
    (comp (ref "D13")
      (value "1N5819HW-7-F")
      (footprint "eagle-import:SOD323-W")
      (libsource (lib "eagle-import") (part "DIODE-SOD323-W"))
    )
    (comp (ref "D14")
      (value "N.C.")
      (footprint "eagle-import:SOD323-W")
      (libsource (lib "eagle-import") (part "DIODE-SOD323-W"))
    )
    (comp (ref "D15")
      (value "C3D02065E")
      (footprint "eagle-import:TO252")
      (libsource (lib "eagle-import") (part "SCHOTTKY-SIC"))
    )
    (comp (ref "D16")
      (value "C3D02065E")
      (footprint "eagle-import:TO252")
      (libsource (lib "eagle-import") (part "SCHOTTKY-SIC"))
    )
    (comp (ref "D17")
      (value "BAS316")
      (footprint "eagle-import:SOD323-R")
      (libsource (lib "eagle-import") (part "DIODESOD323R"))
    )
    (comp (ref "D18")
      (value "BAS316")
      (footprint "eagle-import:SOD323-R")
      (libsource (lib "eagle-import") (part "DIODESOD323R"))
    )
    (comp (ref "D19")
      (value "1N5819HW-7-F")
      (footprint "eagle-import:SOD323-W")
      (libsource (lib "eagle-import") (part "DIODE-SOD323-W"))
    )
    (comp (ref "D20")
      (value "1N5819HW-7-F")
      (footprint "eagle-import:SOD323-W")
      (libsource (lib "eagle-import") (part "DIODE-SOD323-W"))
    )
    (comp (ref "FM1")
      (value "FIDUCIAL_2")
      (footprint "eagle-import:FIDUCIAL_DUAL")
      (libsource (lib "eagle-import") (part "FIDUCIAL_2"))
    )
    (comp (ref "FM2")
      (value "FIDUCIAL_2")
      (footprint "eagle-import:FIDUCIAL_DUAL")
      (libsource (lib "eagle-import") (part "FIDUCIAL_2"))
    )
    (comp (ref "IC2")
      (value "SI8233BB-D-IS1")
      (footprint "eagle-import:SOIC-16")
      (libsource (lib "eagle-import") (part "SI8233"))
    )
    (comp (ref "IC3")
      (value "LM5041B")
      (footprint "eagle-import:MTC16")
      (fields (field (name "MANUFACTURER_PART_NUMBER") "lm5041mtcnopb"))
      (libsource (lib "eagle-import") (part "LM5041"))
    )
    (comp (ref "IC4")
      (value "LM258D")
      (footprint "eagle-import:SOIC127P600X173-8N")
      (libsource (lib "eagle-import") (part "TL072SOIC8"))
    )
    (comp (ref "L5")
      (value "60B684C")
      (footprint "eagle-import:MURATA_6000B")
      (libsource (lib "eagle-import") (part "EEZ_inductors_and_transformers_MURATA_6000B"))
    )
    (comp (ref "L6")
      (value "60B684C")
      (footprint "eagle-import:MURATA_6000B")
      (libsource (lib "eagle-import") (part "EEZ_inductors_and_transformers_MURATA_6000B"))
    )
    (comp (ref "LED2")
      (value "LTST-C170KRKT")
      (footprint "eagle-import:LED_0805")
      (libsource (lib "eagle-import") (part "LED0805"))
    )
    (comp (ref "OK2")
      (value "TLP291-GB.SE-T")
      (footprint "eagle-import:SO4")
      (libsource (lib "eagle-import") (part "TLP291"))
    )
    (comp (ref "Q2")
      (value "C3M0280090D")
      (footprint "eagle-import:TO247BV-ROUND")
      (libsource (lib "eagle-import") (part "N-MOSFETTO247"))
    )
    (comp (ref "Q3")
      (value "C3M0280090D")
      (footprint "eagle-import:TO247BV-ROUND")
      (libsource (lib "eagle-import") (part "N-MOSFETTO247"))
    )
    (comp (ref "Q4")
      (value "C3M0280090D")
      (footprint "eagle-import:TO247BV-ROUND")
      (libsource (lib "eagle-import") (part "N-MOSFETTO247"))
    )
    (comp (ref "Q5")
      (value "NYC0102BLT1G")
      (footprint "eagle-import:SOT23")
      (libsource (lib "eagle-import") (part "NYC0102BLT1G"))
    )
    (comp (ref "Q6")
      (value "C3M0280090D")
      (footprint "eagle-import:TO247BV-ROUND")
      (libsource (lib "eagle-import") (part "N-MOSFETTO247"))
    )
    (comp (ref "R20")
      (value "10K")
      (footprint "eagle-import:R0805")
      (libsource (lib "eagle-import") (part "R-EU_R0805"))
    )
    (comp (ref "R21")
      (value "6R2")
      (footprint "eagle-import:R0805")
      (libsource (lib "eagle-import") (part "R-EU_R0805"))
    )
    (comp (ref "R22")
      (value "N.C.")
      (footprint "eagle-import:R0805")
      (libsource (lib "eagle-import") (part "R-EU_R0805"))
    )
    (comp (ref "R23")
      (value "10R")
      (footprint "eagle-import:R0805")
      (libsource (lib "eagle-import") (part "R-EU_R0805"))
    )
    (comp (ref "R24")
      (value "10R")
      (footprint "eagle-import:R0805")
      (libsource (lib "eagle-import") (part "R-EU_R0805"))
    )
    (comp (ref "R25")
      (value "100R")
      (footprint "eagle-import:R0805")
      (libsource (lib "eagle-import") (part "R-EU_R0805"))
    )
    (comp (ref "R26")
      (value "22R/2-3W")
      (footprint "eagle-import:R2512")
      (libsource (lib "eagle-import") (part "R-EU_R2512"))
    )
    (comp (ref "R27")
      (value "100R")
      (footprint "eagle-import:R0805")
      (libsource (lib "eagle-import") (part "R-EU_R0805"))
    )
    (comp (ref "R28")
      (value "22R/2-3W")
      (footprint "eagle-import:R2512")
      (libsource (lib "eagle-import") (part "R-EU_R2512"))
    )
    (comp (ref "R29")
      (value "1R")
      (footprint "eagle-import:R0805")
      (libsource (lib "eagle-import") (part "R-EU_R0805"))
    )
    (comp (ref "R30")
      (value "30K")
      (footprint "eagle-import:R0805")
      (libsource (lib "eagle-import") (part "R-EU_R0805"))
    )
    (comp (ref "R31")
      (value "10R")
      (footprint "eagle-import:R0805")
      (libsource (lib "eagle-import") (part "R-EU_R0805"))
    )
    (comp (ref "R32")
      (value "220K")
      (footprint "eagle-import:R1206")
      (libsource (lib "eagle-import") (part "R-EU_R1206"))
    )
    (comp (ref "R33")
      (value "10R")
      (footprint "eagle-import:R0805")
      (libsource (lib "eagle-import") (part "R-EU_R0805"))
    )
    (comp (ref "R34")
      (value "10R")
      (footprint "eagle-import:R0805")
      (libsource (lib "eagle-import") (part "R-EU_R0805"))
    )
    (comp (ref "R35")
      (value "47K")
      (footprint "eagle-import:R0805")
      (libsource (lib "eagle-import") (part "R-EU_R0805"))
    )
    (comp (ref "R36")
      (value "1K")
      (footprint "eagle-import:R0805")
      (libsource (lib "eagle-import") (part "R-EU_R0805"))
    )
    (comp (ref "R37")
      (value "1R")
      (footprint "eagle-import:R0805")
      (libsource (lib "eagle-import") (part "R-EU_R0805"))
    )
    (comp (ref "R38")
      (value "22R/2-3W")
      (footprint "eagle-import:R2512")
      (libsource (lib "eagle-import") (part "R-EU_R2512"))
    )
    (comp (ref "R39")
      (value "22R/2-3W")
      (footprint "eagle-import:R2512")
      (libsource (lib "eagle-import") (part "R-EU_R2512"))
    )
    (comp (ref "R40")
      (value "100K")
      (footprint "eagle-import:R0805")
      (libsource (lib "eagle-import") (part "R-EU_R0805"))
    )
    (comp (ref "R41")
      (value "10R")
      (footprint "eagle-import:R0805")
      (libsource (lib "eagle-import") (part "R-EU_R0805"))
    )
    (comp (ref "R42")
      (value "1K")
      (footprint "eagle-import:R0805")
      (libsource (lib "eagle-import") (part "R-EU_R0805"))
    )
    (comp (ref "R43")
      (value "6K8")
      (footprint "eagle-import:R0805")
      (libsource (lib "eagle-import") (part "R-EU_R0805"))
    )
    (comp (ref "R44")
      (value "22R")
      (footprint "eagle-import:R0805")
      (libsource (lib "eagle-import") (part "R-EU_R0805"))
    )
    (comp (ref "R45")
      (value "22R")
      (footprint "eagle-import:R0805")
      (libsource (lib "eagle-import") (part "R-EU_R0805"))
    )
    (comp (ref "R46")
      (value "1K")
      (footprint "eagle-import:R0805")
      (libsource (lib "eagle-import") (part "R-EU_R0805"))
    )
    (comp (ref "R47")
      (value "30K")
      (footprint "eagle-import:R0805")
      (libsource (lib "eagle-import") (part "R-EU_R0805"))
    )
    (comp (ref "R48")
      (value "82K")
      (footprint "eagle-import:R0805")
      (libsource (lib "eagle-import") (part "R-EU_R0805"))
    )
    (comp (ref "R49")
      (value "1K")
      (footprint "eagle-import:R0805")
      (libsource (lib "eagle-import") (part "R-EU_R0805"))
    )
    (comp (ref "R50")
      (value "N.C.")
      (footprint "eagle-import:R0805")
      (libsource (lib "eagle-import") (part "R-EU_R0805"))
    )
    (comp (ref "R51")
      (value "4K7")
      (footprint "eagle-import:R0805")
      (libsource (lib "eagle-import") (part "R-EU_R0805"))
    )
    (comp (ref "R52")
      (value "1K")
      (footprint "eagle-import:R0805")
      (libsource (lib "eagle-import") (part "R-EU_R0805"))
    )
    (comp (ref "R53")
      (value "30K")
      (footprint "eagle-import:R0805")
      (libsource (lib "eagle-import") (part "R-EU_R0805"))
    )
    (comp (ref "R54")
      (value "10K")
      (footprint "eagle-import:R0805")
      (libsource (lib "eagle-import") (part "R-EU_R0805"))
    )
    (comp (ref "SH1")
      (value "SHORTNOHOLE")
      (footprint "eagle-import:SHORT_NOHOLE")
      (libsource (lib "eagle-import") (part "SHORTNOHOLE"))
    )
    (comp (ref "TP3")
      (value "PCB_TEST_TABSHIELD")
      (footprint "eagle-import:PCB_SHIELD_TAB")
      (libsource (lib "eagle-import") (part "PCB_TEST_TABSHIELD"))
    )
    (comp (ref "TP4")
      (value "PCB_TEST_TABSHIELD")
      (footprint "eagle-import:PCB_SHIELD_TAB")
      (libsource (lib "eagle-import") (part "PCB_TEST_TABSHIELD"))
    )
    (comp (ref "TP5")
      (value "PCB_TEST_TABSHIELD")
      (footprint "eagle-import:PCB_SHIELD_TAB")
      (libsource (lib "eagle-import") (part "PCB_TEST_TABSHIELD"))
    )
    (comp (ref "TR2")
      (value "53100C")
      (footprint "eagle-import:MURATA_5300")
      (libsource (lib "eagle-import") (part "MURATA_5300"))
    )
    (comp (ref "TR3")
      (value "VAC T60006-L2025-W380")
      (footprint "eagle-import:VAC_DUAL_SEC")
      (libsource (lib "eagle-import") (part "PCB_TRAFO_FLYBACK2-VAC"))
    )
    (comp (ref "X4")
      (value "B2B-ZR")
      (footprint "eagle-import:B2B-ZR")
      (libsource (lib "eagle-import") (part "B2B-ZR"))
    )
    (comp (ref "ZD4")
      (value "MMSZ5V1T1G")
      (footprint "eagle-import:SOD323-W")
      (libsource (lib "eagle-import") (part "ZENER-DIODESOD323"))
    )
    (comp (ref "ZD5")
      (value "PDZ6.2B")
      (footprint "eagle-import:SOD323-W")
      (libsource (lib "eagle-import") (part "ZENER-DIODESOD323"))
    )
  )
  (nets
    (net (code "1") (name "+2.5VREF") (class "Default")
      (node (ref "C71") (pin "1") (pinfunction "1_1") (pintype "passive"))
      (node (ref "IC7") (pin "3") (pinfunction "+IN1_3") (pintype "input"))
      (node (ref "P1") (pin "E") (pinfunction "E_E") (pintype "passive"))
      (node (ref "R67") (pin "2") (pinfunction "2_2") (pintype "passive"))
      (node (ref "R72") (pin "1") (pinfunction "1_1") (pintype "passive"))
    )
    (net (code "2") (name "+5VREF") (class "Default")
      (node (ref "C45") (pin "2") (pinfunction "2_2") (pintype "passive"))
      (node (ref "C50") (pin "1") (pinfunction "1_1") (pintype "passive"))
      (node (ref "IC3") (pin "4") (pinfunction "REF_4") (pintype "output"))
      (node (ref "R33") (pin "1") (pinfunction "1_1") (pintype "passive"))
      (node (ref "R51") (pin "2") (pinfunction "2_2") (pintype "passive"))
      (node (ref "X4") (pin "1") (pinfunction "1_1") (pintype "passive"))
    )
    (net (code "3") (name "+12V") (class "Default")
      (node (ref "C26") (pin "2") (pinfunction "2_2") (pintype "passive"))
      (node (ref "C27") (pin "2") (pinfunction "2_2") (pintype "passive"))
      (node (ref "C49") (pin "1") (pinfunction "1_1") (pintype "passive"))
      (node (ref "C6") (pin "1") (pinfunction "1_1") (pintype "passive"))
      (node (ref "IC4") (pin "8") (pinfunction "V+_8") (pintype "power_in"))
      (node (ref "OK2") (pin "1") (pinfunction "A_1") (pintype "passive"))
      (node (ref "Q1") (pin "E") (pinfunction "E_E") (pintype "passive"))
      (node (ref "R23") (pin "2") (pinfunction "2_2") (pintype "passive"))
      (node (ref "R34") (pin "2") (pinfunction "2_2") (pintype "passive"))
      (node (ref "R41") (pin "2") (pinfunction "2_2") (pintype "passive"))
      (node (ref "X2") (pin "1") (pinfunction "1_1") (pintype "passive"))
    )
    (net (code "4") (name "0V") (class "Default")
      (node (ref "C13") (pin "-") (pinfunction "-_-") (pintype "passive"))
      (node (ref "C18") (pin "1") (pinfunction "1_1") (pintype "passive"))
      (node (ref "C21") (pin "2") (pinfunction "-_2") (pintype "passive"))
      (node (ref "C24") (pin "2") (pinfunction "2_2") (pintype "passive"))
      (node (ref "C25") (pin "2") (pinfunction "2_2") (pintype "passive"))
      (node (ref "C26") (pin "1") (pinfunction "1_1") (pintype "passive"))
      (node (ref "C27") (pin "1") (pinfunction "1_1") (pintype "passive"))
      (node (ref "C28") (pin "-") (pinfunction "-_-") (pintype "passive"))
      (node (ref "C29") (pin "-") (pinfunction "-_-") (pintype "passive"))
      (node (ref "C33") (pin "1") (pinfunction "1_1") (pintype "passive"))
      (node (ref "C34") (pin "1") (pinfunction "1_1") (pintype "passive"))
      (node (ref "C35") (pin "2") (pinfunction "2_2") (pintype "passive"))
      (node (ref "C36") (pin "2") (pinfunction "2_2") (pintype "passive"))
      (node (ref "C37") (pin "2") (pinfunction "2_2") (pintype "passive"))
      (node (ref "C39") (pin "2") (pinfunction "2_2") (pintype "passive"))
      (node (ref "C40") (pin "2") (pinfunction "2_2") (pintype "passive"))
      (node (ref "C41") (pin "2") (pinfunction "2_2") (pintype "passive"))
      (node (ref "C42") (pin "1") (pinfunction "1_1") (pintype "passive"))
      (node (ref "C43") (pin "1") (pinfunction "1_1") (pintype "passive"))
      (node (ref "C44") (pin "1") (pinfunction "1_1") (pintype "passive"))
      (node (ref "C45") (pin "1") (pinfunction "1_1") (pintype "passive"))
      (node (ref "C46") (pin "1") (pinfunction "1_1") (pintype "passive"))
      (node (ref "C47") (pin "1") (pinfunction "1_1") (pintype "passive"))
      (node (ref "C48") (pin "1") (pinfunction "1_1") (pintype "passive"))
      (node (ref "C49") (pin "2") (pinfunction "2_2") (pintype "passive"))
      (node (ref "C50") (pin "2") (pinfunction "2_2") (pintype "passive"))
      (node (ref "C6") (pin "2") (pinfunction "2_2") (pintype "passive"))
      (node (ref "C7") (pin "2") (pinfunction "-_2") (pintype "passive"))
      (node (ref "C8") (pin "2") (pinfunction "2_2") (pintype "passive"))
      (node (ref "D12") (pin "2") (pinfunction "A_2") (pintype "passive"))
      (node (ref "D8") (pin "A") (pinfunction "A_A") (pintype "passive"))
      (node (ref "IC1") (pin "1") (pinfunction "GND_1") (pintype "passive"))
      (node (ref "IC1") (pin "2") (pinfunction "GND_2") (pintype "passive"))
      (node (ref "IC1") (pin "3") (pinfunction "GND_3") (pintype "passive"))
      (node (ref "IC1") (pin "4") (pinfunction "GND_4") (pintype "passive"))
      (node (ref "IC2") (pin "4") (pinfunction "GNDI_4") (pintype "power_in"))
      (node (ref "IC2") (pin "5") (pinfunction "DISABLE_5") (pintype "input"))
      (node (ref "IC2") (pin "9") (pinfunction "GNDB_9") (pintype "power_in"))
      (node (ref "IC3") (pin "10") (pinfunction "PGND_10") (pintype "power_in"))
      (node (ref "IC3") (pin "11") (pinfunction "AGND_11") (pintype "power_in"))
      (node (ref "IC3") (pin "2") (pinfunction "FB_2") (pintype "input"))
      (node (ref "IC4") (pin "4") (pinfunction "V-_4") (pintype "power_in"))
      (node (ref "JP2") (pin "NO") (pinfunction "NO_NO") (pintype "passive"))
      (node (ref "OK1") (pin "3") (pinfunction "EMIT_3") (pintype "passive"))
      (node (ref "OK3") (pin "3") (pinfunction "EMIT_3") (pintype "passive"))
      (node (ref "Q3") (pin "S") (pinfunction "S_S") (pintype "passive"))
      (node (ref "Q4") (pin "S") (pinfunction "S_S") (pintype "passive"))
      (node (ref "Q5") (pin "1") (pinfunction "C_1") (pintype "passive"))
      (node (ref "Q6") (pin "S") (pinfunction "S_S") (pintype "passive"))
      (node (ref "R16") (pin "1") (pinfunction "1_1") (pintype "passive"))
      (node (ref "R17") (pin "2") (pinfunction "2_2") (pintype "passive"))
      (node (ref "R18") (pin "2") (pinfunction "2_2") (pintype "passive"))
      (node (ref "R20") (pin "2") (pinfunction "2_2") (pintype "passive"))
      (node (ref "R21") (pin "2") (pinfunction "2_2") (pintype "passive"))
      (node (ref "R22") (pin "2") (pinfunction "2_2") (pintype "passive"))
      (node (ref "R29") (pin "1") (pinfunction "1_1") (pintype "passive"))
      (node (ref "R29") (pin "2") (pinfunction "2_2") (pintype "passive"))
      (node (ref "R30") (pin "1") (pinfunction "1_1") (pintype "passive"))
      (node (ref "R35") (pin "2") (pinfunction "2_2") (pintype "passive"))
      (node (ref "R37") (pin "1") (pinfunction "1_1") (pintype "passive"))
      (node (ref "R37") (pin "2") (pinfunction "2_2") (pintype "passive"))
      (node (ref "R43") (pin "2") (pinfunction "2_2") (pintype "passive"))
      (node (ref "R47") (pin "2") (pinfunction "2_2") (pintype "passive"))
      (node (ref "R48") (pin "2") (pinfunction "2_2") (pintype "passive"))
      (node (ref "R52") (pin "2") (pinfunction "2_2") (pintype "passive"))
      (node (ref "R53") (pin "2") (pinfunction "2_2") (pintype "passive"))
      (node (ref "R54") (pin "2") (pinfunction "2_2") (pintype "passive"))
      (node (ref "SH1") (pin "P$2") (pinfunction "GND_B_P$2") (pintype "bidirectional"))
      (node (ref "TP1") (pin "1") (pinfunction "P$1_1") (pintype "bidirectional"))
      (node (ref "TP4") (pin "1") (pinfunction "P$1_1") (pintype "bidirectional"))
      (node (ref "TR1") (pin "6") (pinfunction "S_BIAS_6") (pintype "passive"))
      (node (ref "TR2") (pin "3") (pinfunction "S_3") (pintype "passive"))
      (node (ref "X2") (pin "2") (pinfunction "1_2") (pintype "passive"))
      (node (ref "ZD1") (pin "A") (pinfunction "A_A") (pintype "passive"))
      (node (ref "ZD2") (pin "A") (pinfunction "A_A") (pintype "passive"))
      (node (ref "ZD4") (pin "A") (pinfunction "A_A") (pintype "passive"))
      (node (ref "ZD5") (pin "A") (pinfunction "A_A") (pintype "passive"))
    )
    (net (code "5") (name "AC_L_IN") (class "Default")
      (node (ref "C1") (pin "1") (pinfunction "1_1") (pintype "passive"))
      (node (ref "C4A") (pin "2") (pinfunction "2_2") (pintype "passive"))
      (node (ref "L1") (pin "2") (pinfunction "2_2") (pintype "passive"))
      (node (ref "R1") (pin "1") (pinfunction "1_1") (pintype "passive"))
      (node (ref "SAR1") (pin "1") (pinfunction "P$1_1") (pintype "bidirectional"))
      (node (ref "X1") (pin "1") (pinfunction "1_1") (pintype "passive"))
    )
    (net (code "6") (name "AC_N_IN") (class "Default")
      (node (ref "C1") (pin "2") (pinfunction "2_2") (pintype "passive"))
      (node (ref "C5A") (pin "2") (pinfunction "2_2") (pintype "passive"))
      (node (ref "L1") (pin "4") (pinfunction "2_4") (pintype "passive"))
      (node (ref "R2") (pin "2") (pinfunction "2_2") (pintype "passive"))
      (node (ref "SAR2") (pin "1") (pinfunction "P$1_1") (pintype "bidirectional"))
      (node (ref "X1") (pin "2") (pinfunction "1_2") (pintype "passive"))
    )
    (net (code "7") (name "AUX_AC") (class "Default")
      (node (ref "C3") (pin "2") (pinfunction "2_2") (pintype "passive"))
      (node (ref "D1") (pin "A") (pinfunction "A_A") (pintype "passive"))
      (node (ref "D6") (pin "A") (pinfunction "A_A") (pintype "passive"))
      (node (ref "D7") (pin "A") (pinfunction "A_A") (pintype "passive"))
      (node (ref "R13") (pin "2") (pinfunction "2_2") (pintype "passive"))
      (node (ref "TR1") (pin "7") (pinfunction "S_BIAS_DOT_7") (pintype "passive"))
    )
    (net (code "8") (name "BUCK_OUT") (class "Default")
      (node (ref "C30") (pin "2") (pinfunction "2_2") (pintype "passive"))
      (node (ref "C31") (pin "2") (pinfunction "2_2") (pintype "passive"))
      (node (ref "C32") (pin "2") (pinfunction "2_2") (pintype "passive"))
      (node (ref "D12") (pin "1") (pinfunction "C_1") (pintype "passive"))
      (node (ref "IC2") (pin "14") (pinfunction "GNDA_14") (pintype "power_in"))
      (node (ref "L5") (pin "2") (pinfunction "P$2_2") (pintype "bidirectional"))
      (node (ref "L6") (pin "2") (pinfunction "P$2_2") (pintype "bidirectional"))
      (node (ref "Q2") (pin "S") (pinfunction "S_S") (pintype "passive"))
      (node (ref "Q3") (pin "D") (pinfunction "D_D") (pintype "passive"))
      (node (ref "TP3") (pin "1") (pinfunction "P$1_1") (pintype "bidirectional"))
    )
    (net (code "9") (name "CT_OUT") (class "Default")
      (node (ref "D9") (pin "C") (pinfunction "C_C") (pintype "passive"))
      (node (ref "R21") (pin "1") (pinfunction "1_1") (pintype "passive"))
      (node (ref "R22") (pin "1") (pinfunction "1_1") (pintype "passive"))
      (node (ref "R49") (pin "1") (pinfunction "1_1") (pintype "passive"))
    )
    (net (code "10") (name "DC_BUS") (class "Default")
      (node (ref "B1") (pin "+") (pinfunction "+_+") (pintype "passive"))
      (node (ref "C12") (pin "1") (pinfunction "1_1") (pintype "passive"))
      (node (ref "C13") (pin "+") (pinfunction "+_+") (pintype "passive"))
      (node (ref "C28") (pin "+") (pinfunction "+_+") (pintype "passive"))
      (node (ref "C29") (pin "+") (pinfunction "+_+") (pintype "passive"))
      (node (ref "C33") (pin "2") (pinfunction "2_2") (pintype "passive"))
      (node (ref "R32") (pin "1") (pinfunction "1_1") (pintype "passive"))
      (node (ref "R38") (pin "2") (pinfunction "2_2") (pintype "passive"))
      (node (ref "R39") (pin "2") (pinfunction "2_2") (pintype "passive"))
      (node (ref "R6") (pin "1") (pinfunction "1_1") (pintype "passive"))
      (node (ref "R7") (pin "1") (pinfunction "1_1") (pintype "passive"))
      (node (ref "TR1") (pin "1") (pinfunction "SHIELD_1") (pintype "passive"))
      (node (ref "TR1") (pin "2") (pinfunction "P_2") (pintype "passive"))
      (node (ref "TR2") (pin "8") (pinfunction "P_DOT_8") (pintype "passive"))
    )
    (net (code "11") (name "DC_OUT") (class "Default")
      (node (ref "C11") (pin "1") (pinfunction "1_1") (pintype "passive"))
      (node (ref "L2") (pin "2") (pinfunction "2_2") (pintype "passive"))
      (node (ref "X3") (pin "2") (pinfunction "S_2") (pintype "passive"))
    )
    (net (code "12") (name "GND") (class "Default")
      (node (ref "C14") (pin "1") (pinfunction "+_1") (pintype "passive"))
      (node (ref "C15") (pin "1") (pinfunction "1_1") (pintype "passive"))
      (node (ref "C17") (pin "2") (pinfunction "2_2") (pintype "passive"))
      (node (ref "C20") (pin "-") (pinfunction "-_-") (pintype "passive"))
      (node (ref "C22") (pin "2") (pinfunction "2_2") (pintype "passive"))
      (node (ref "C51") (pin "-") (pinfunction "-_-") (pintype "passive"))
      (node (ref "C52") (pin "-") (pinfunction "-_-") (pintype "passive"))
      (node (ref "C53") (pin "-") (pinfunction "-_-") (pintype "passive"))
      (node (ref "C54") (pin "2") (pinfunction "2_2") (pintype "passive"))
      (node (ref "C55") (pin "2") (pinfunction "2_2") (pintype "passive"))
      (node (ref "C56") (pin "2") (pinfunction "2_2") (pintype "passive"))
      (node (ref "C57") (pin "2") (pinfunction "2_2") (pintype "passive"))
      (node (ref "C58") (pin "2") (pinfunction "2_2") (pintype "passive"))
      (node (ref "C59") (pin "1") (pinfunction "1_1") (pintype "passive"))
      (node (ref "C60") (pin "2") (pinfunction "2_2") (pintype "passive"))
      (node (ref "C61") (pin "2") (pinfunction "2_2") (pintype "passive"))
      (node (ref "C62") (pin "2") (pinfunction "2_2") (pintype "passive"))
      (node (ref "C63") (pin "2") (pinfunction "2_2") (pintype "passive"))
      (node (ref "C64") (pin "2") (pinfunction "2_2") (pintype "passive"))
      (node (ref "C65") (pin "2") (pinfunction "2_2") (pintype "passive"))
      (node (ref "C66") (pin "2") (pinfunction "2_2") (pintype "passive"))
      (node (ref "C70") (pin "-") (pinfunction "-_-") (pintype "passive"))
      (node (ref "C71") (pin "2") (pinfunction "2_2") (pintype "passive"))
      (node (ref "IC5") (pin "6") (pinfunction "VS_6") (pintype "passive"))
      (node (ref "IC5") (pin "7") (pinfunction "GND_7") (pintype "power_in"))
      (node (ref "IC6") (pin "3") (pinfunction "+IN_3") (pintype "input"))
      (node (ref "IC6") (pin "5") (pinfunction "+IN_5") (pintype "input"))
      (node (ref "IC7") (pin "4") (pinfunction "VCC-_4") (pintype "power_in"))
      (node (ref "JP1") (pin "NO") (pinfunction "NO_NO") (pintype "passive"))
      (node (ref "LED1") (pin "C") (pinfunction "C_C") (pintype "passive"))
      (node (ref "OK2") (pin "3") (pinfunction "EMIT_3") (pintype "passive"))
      (node (ref "P1") (pin "A") (pinfunction "A_A") (pintype "passive"))
      (node (ref "Q7") (pin "2") (pinfunction "S_2") (pintype "passive"))
      (node (ref "Q8") (pin "2") (pinfunction "S_2") (pintype "passive"))
      (node (ref "R61") (pin "2") (pinfunction "2_2") (pintype "passive"))
      (node (ref "TP2") (pin "1") (pinfunction "P$1_1") (pintype "bidirectional"))
      (node (ref "TP6") (pin "GND") (pinfunction "GND_GND") (pintype "bidirectional"))
      (node (ref "TR1") (pin "10") (pinfunction "S1_10") (pintype "passive"))
      (node (ref "TR1") (pin "11") (pinfunction "S1_11") (pintype "passive"))
      (node (ref "TR1") (pin "9") (pinfunction "S2_DOT_9") (pintype "passive"))
      (node (ref "X3") (pin "6") (pinfunction "S_6") (pintype "passive"))
      (node (ref "X5") (pin "2") (pinfunction "1_2") (pintype "passive"))
      (node (ref "ZD3") (pin "A") (pinfunction "A_A") (pintype "passive"))
      (node (ref "ZD6") (pin "A") (pinfunction "A_A") (pintype "passive"))
    )
    (net (code "13") (name "GNDA") (class "Default")
      (node (ref "B1") (pin "-") (pinfunction "-_-") (pintype "passive"))
      (node (ref "SH1") (pin "P$1") (pinfunction "GND_A_P$1") (pintype "bidirectional"))
    )
    (net (code "14") (name "HD") (class "Default")
      (node (ref "IC3") (pin "5") (pinfunction "HD_5") (pintype "output"))
      (node (ref "R25") (pin "2") (pinfunction "2_2") (pintype "passive"))
    )
    (net (code "15") (name "HI_OUT") (class "Default")
      (node (ref "D11") (pin "A") (pinfunction "A_A") (pintype "passive"))
      (node (ref "IC2") (pin "15") (pinfunction "VOA_15") (pintype "output"))
      (node (ref "R24") (pin "2") (pinfunction "2_2") (pintype "passive"))
    )
    (net (code "16") (name "ISO_FB") (class "Default")
      (node (ref "C46") (pin "2") (pinfunction "2_2") (pintype "passive"))
      (node (ref "IC3") (pin "3") (pinfunction "COMP_3") (pintype "passive"))
      (node (ref "OK3") (pin "4") (pinfunction "COL_4") (pintype "passive"))
      (node (ref "R50") (pin "1") (pinfunction "1_1") (pintype "passive"))
      (node (ref "TP5") (pin "1") (pinfunction "P$1_1") (pintype "bidirectional"))
    )
    (net (code "17") (name "LD") (class "Default")
      (node (ref "IC3") (pin "6") (pinfunction "LD_6") (pintype "output"))
      (node (ref "R27") (pin "2") (pinfunction "2_2") (pintype "passive"))
    )
    (net (code "18") (name "LO_OUT") (class "Default")
      (node (ref "D14") (pin "A") (pinfunction "A_A") (pintype "passive"))
      (node (ref "IC2") (pin "10") (pinfunction "VOB_10") (pintype "output"))
      (node (ref "R31") (pin "1") (pinfunction "1_1") (pintype "passive"))
    )
    (net (code "19") (name "Net-(C3-Pad1)") (class "Default")
      (node (ref "C3") (pin "1") (pinfunction "1_1") (pintype "passive"))
      (node (ref "R3") (pin "2") (pinfunction "2_2") (pintype "passive"))
    )
    (net (code "20") (name "Net-(C7-+)") (class "Default")
      (node (ref "C7") (pin "1") (pinfunction "+_1") (pintype "passive"))
      (node (ref "D1") (pin "C") (pinfunction "C_C") (pintype "passive"))
      (node (ref "Q1") (pin "C") (pinfunction "C_C") (pintype "passive"))
      (node (ref "R3") (pin "1") (pinfunction "1_1") (pintype "passive"))
      (node (ref "R4") (pin "1") (pinfunction "1_1") (pintype "passive"))
    )
    (net (code "21") (name "Net-(C8-Pad1)") (class "Default")
      (node (ref "C8") (pin "1") (pinfunction "1_1") (pintype "passive"))
      (node (ref "Q1") (pin "B") (pinfunction "B_B") (pintype "passive"))
      (node (ref "R4") (pin "2") (pinfunction "2_2") (pintype "passive"))
      (node (ref "ZD1") (pin "C") (pinfunction "C_C") (pintype "passive"))
    )
    (net (code "22") (name "Net-(C9-Pad1)") (class "Default")
      (node (ref "C9") (pin "1") (pinfunction "1_1") (pintype "passive"))
      (node (ref "R5") (pin "2") (pinfunction "2_2") (pintype "passive"))
    )
    (net (code "23") (name "Net-(C10-+)") (class "Default")
      (node (ref "C10") (pin "1") (pinfunction "+_1") (pintype "passive"))
      (node (ref "D2") (pin "C") (pinfunction "C_C") (pintype "passive"))
      (node (ref "L2") (pin "1") (pinfunction "1_1") (pintype "passive"))
      (node (ref "R5") (pin "1") (pinfunction "1_1") (pintype "passive"))
    )
    (net (code "24") (name "Net-(C10--)") (class "Default")
      (node (ref "C10") (pin "2") (pinfunction "-_2") (pintype "passive"))
      (node (ref "C11") (pin "2") (pinfunction "2_2") (pintype "passive"))
      (node (ref "JP1") (pin "COM") (pinfunction "COM_COM") (pintype "passive"))
      (node (ref "TR1") (pin "14") (pinfunction "S3_14") (pintype "passive"))
      (node (ref "X3") (pin "3") (pinfunction "S_3") (pintype "passive"))
    )
    (net (code "25") (name "Net-(C12-Pad2)") (class "Default")
      (node (ref "C12") (pin "2") (pinfunction "2_2") (pintype "passive"))
      (node (ref "D3") (pin "C") (pinfunction "C_C") (pintype "passive"))
      (node (ref "R6") (pin "2") (pinfunction "2_2") (pintype "passive"))
    )
    (net (code "26") (name "Net-(C14--)") (class "Default")
      (node (ref "C14") (pin "2") (pinfunction "-_2") (pintype "passive"))
      (node (ref "D4") (pin "A") (pinfunction "A_A") (pintype "passive"))
      (node (ref "L3") (pin "1") (pinfunction "1_1") (pintype "passive"))
      (node (ref "R9") (pin "1") (pinfunction "1_1") (pintype "passive"))
    )
    (net (code "27") (name "Net-(C16-Pad1)") (class "Default")
      (node (ref "C16") (pin "1") (pinfunction "1_1") (pintype "passive"))
      (node (ref "R9") (pin "2") (pinfunction "2_2") (pintype "passive"))
    )
    (net (code "28") (name "Net-(C17-Pad1)") (class "Default")
      (node (ref "C17") (pin "1") (pinfunction "1_1") (pintype "passive"))
      (node (ref "JP2") (pin "COM") (pinfunction "COM_COM") (pintype "passive"))
    )
    (net (code "29") (name "Net-(C19-Pad1)") (class "Default")
      (node (ref "C19") (pin "1") (pinfunction "1_1") (pintype "passive"))
      (node (ref "R10") (pin "2") (pinfunction "2_2") (pintype "passive"))
    )
    (net (code "30") (name "Net-(C19-Pad2)") (class "Default")
      (node (ref "C19") (pin "2") (pinfunction "2_2") (pintype "passive"))
      (node (ref "D5") (pin "A") (pinfunction "A_A") (pintype "passive"))
      (node (ref "TR1") (pin "12") (pinfunction "S1_DOT_12") (pintype "passive"))
      (node (ref "TR1") (pin "13") (pinfunction "S1_DOT_13") (pintype "passive"))
    )
    (net (code "31") (name "Net-(C20-Pad+)") (class "Default")
      (node (ref "C20") (pin "+") (pinfunction "+_+") (pintype "passive"))
      (node (ref "D5") (pin "C") (pinfunction "C_C") (pintype "passive"))
      (node (ref "L4") (pin "1") (pinfunction "1_1") (pintype "passive"))
      (node (ref "R10") (pin "1") (pinfunction "1_1") (pintype "passive"))
      (node (ref "R15") (pin "1") (pinfunction "1_1") (pintype "passive"))
    )
    (net (code "32") (name "Net-(C21-+)") (class "Default")
      (node (ref "C18") (pin "2") (pinfunction "2_2") (pintype "passive"))
      (node (ref "C21") (pin "1") (pinfunction "+_1") (pintype "passive"))
      (node (ref "D6") (pin "C") (pinfunction "C_C") (pintype "passive"))
      (node (ref "IC1") (pin "5") (pinfunction "VDD_5") (pintype "power_in"))
      (node (ref "ZD2") (pin "C") (pinfunction "C_C") (pintype "passive"))
    )
    (net (code "33") (name "Net-(C23-Pad1)") (class "Default")
      (node (ref "C23") (pin "1") (pinfunction "1_1") (pintype "passive"))
      (node (ref "R18") (pin "1") (pinfunction "1_1") (pintype "passive"))
    )
    (net (code "34") (name "Net-(C38-Pad1)") (class "Default")
      (node (ref "C38") (pin "1") (pinfunction "1_1") (pintype "passive"))
      (node (ref "R28") (pin "1") (pinfunction "1_1") (pintype "passive"))
    )
    (net (code "35") (name "Net-(C39-Pad1)") (class "Default")
      (node (ref "C39") (pin "1") (pinfunction "1_1") (pintype "passive"))
      (node (ref "D18") (pin "A") (pinfunction "A_A") (pintype "passive"))
      (node (ref "R40") (pin "2") (pinfunction "2_2") (pintype "passive"))
      (node (ref "R42") (pin "2") (pinfunction "2_2") (pintype "passive"))
      (node (ref "R43") (pin "1") (pinfunction "1_1") (pintype "passive"))
    )
    (net (code "36") (name "Net-(C43-Pad2)") (class "Default")
      (node (ref "C43") (pin "2") (pinfunction "2_2") (pintype "passive"))
      (node (ref "C44") (pin "2") (pinfunction "2_2") (pintype "passive"))
      (node (ref "D15") (pin "1") (pinfunction "C_1") (pintype "passive"))
      (node (ref "D15") (pin "3") (pinfunction "C_3") (pintype "passive"))
      (node (ref "D16") (pin "1") (pinfunction "C_1") (pintype "passive"))
      (node (ref "D16") (pin "3") (pinfunction "C_3") (pintype "passive"))
      (node (ref "R38") (pin "1") (pinfunction "1_1") (pintype "passive"))
      (node (ref "R39") (pin "1") (pinfunction "1_1") (pintype "passive"))
    )
    (net (code "37") (name "Net-(C48-Pad2)") (class "Default")
      (node (ref "C48") (pin "2") (pinfunction "2_2") (pintype "passive"))
      (node (ref "R50") (pin "2") (pinfunction "2_2") (pintype "passive"))
    )
    (net (code "38") (name "Net-(C59-Pad2)") (class "Default")
      (node (ref "C59") (pin "2") (pinfunction "2_2") (pintype "passive"))
      (node (ref "R56") (pin "1") (pinfunction "1_1") (pintype "passive"))
    )
    (net (code "39") (name "Net-(C60-Pad1)") (class "Default")
      (node (ref "C60") (pin "1") (pinfunction "1_1") (pintype "passive"))
      (node (ref "R57") (pin "2") (pinfunction "2_2") (pintype "passive"))
      (node (ref "R58") (pin "2") (pinfunction "2_2") (pintype "passive"))
    )
    (net (code "40") (name "Net-(C64-Pad1)") (class "Default")
      (node (ref "C64") (pin "1") (pinfunction "1_1") (pintype "passive"))
      (node (ref "R63") (pin "2") (pinfunction "2_2") (pintype "passive"))
      (node (ref "R64") (pin "2") (pinfunction "2_2") (pintype "passive"))
    )
    (net (code "41") (name "Net-(C69-Pad2)") (class "Default")
      (node (ref "C69") (pin "2") (pinfunction "2_2") (pintype "passive"))
      (node (ref "R74") (pin "2") (pinfunction "2_2") (pintype "passive"))
    )
    (net (code "42") (name "Net-(C70-Pad+)") (class "Default")
      (node (ref "C70") (pin "+") (pinfunction "+_+") (pintype "passive"))
      (node (ref "R68") (pin "1") (pinfunction "1_1") (pintype "passive"))
      (node (ref "R76") (pin "1") (pinfunction "1_1") (pintype "passive"))
      (node (ref "R77") (pin "1") (pinfunction "1_1") (pintype "passive"))
    )
    (net (code "43") (name "Net-(D7-PadC)") (class "Default")
      (node (ref "D7") (pin "C") (pinfunction "C_C") (pintype "passive"))
      (node (ref "D8") (pin "C") (pinfunction "C_C") (pintype "passive"))
      (node (ref "R14") (pin "2") (pinfunction "2_2") (pintype "passive"))
    )
    (net (code "44") (name "Net-(D10-A)") (class "Default")
      (node (ref "D10") (pin "2") (pinfunction "A_2") (pintype "passive"))
      (node (ref "R23") (pin "1") (pinfunction "1_1") (pintype "passive"))
    )
    (net (code "45") (name "Net-(D11-PadC)") (class "Default")
      (node (ref "D11") (pin "C") (pinfunction "C_C") (pintype "passive"))
      (node (ref "Q2") (pin "G") (pinfunction "G_G") (pintype "passive"))
      (node (ref "R24") (pin "1") (pinfunction "1_1") (pintype "passive"))
    )
    (net (code "46") (name "Net-(D13-PadA)") (class "Default")
      (node (ref "D13") (pin "A") (pinfunction "A_A") (pintype "passive"))
      (node (ref "R34") (pin "1") (pinfunction "1_1") (pintype "passive"))
    )
    (net (code "47") (name "Net-(D14-PadC)") (class "Default")
      (node (ref "D14") (pin "C") (pinfunction "C_C") (pintype "passive"))
      (node (ref "Q3") (pin "G") (pinfunction "G_G") (pintype "passive"))
      (node (ref "R31") (pin "2") (pinfunction "2_2") (pintype "passive"))
      (node (ref "R35") (pin "1") (pinfunction "1_1") (pintype "passive"))
    )
    (net (code "48") (name "Net-(D15-A)") (class "Default")
      (node (ref "D15") (pin "2") (pinfunction "A_2") (pintype "passive"))
      (node (ref "L5") (pin "1") (pinfunction "P$1_1") (pintype "bidirectional"))
      (node (ref "Q6") (pin "D") (pinfunction "D_D") (pintype "passive"))
      (node (ref "R26") (pin "2") (pinfunction "2_2") (pintype "passive"))
      (node (ref "TR3") (pin "P1") (pinfunction "P_P1") (pintype "passive"))
    )
    (net (code "49") (name "Net-(D16-A)") (class "Default")
      (node (ref "C38") (pin "2") (pinfunction "2_2") (pintype "passive"))
      (node (ref "D16") (pin "2") (pinfunction "A_2") (pintype "passive"))
      (node (ref "L6") (pin "1") (pinfunction "P$1_1") (pintype "bidirectional"))
      (node (ref "Q4") (pin "D") (pinfunction "D_D") (pintype "passive"))
      (node (ref "TR3") (pin "P1_DOT") (pinfunction "P_DOT_P1_DOT") (pintype "passive"))
    )
    (net (code "50") (name "Net-(D17-PadA)") (class "Default")
      (node (ref "D17") (pin "A") (pinfunction "A_A") (pintype "passive"))
      (node (ref "LED2") (pin "C") (pinfunction "C_C") (pintype "passive"))
    )
    (net (code "51") (name "Net-(D19-PadC)") (class "Default")
      (node (ref "D19") (pin "C") (pinfunction "C_C") (pintype "passive"))
      (node (ref "Q4") (pin "G") (pinfunction "G_G") (pintype "passive"))
      (node (ref "R44") (pin "1") (pinfunction "1_1") (pintype "passive"))
    )
    (net (code "52") (name "Net-(D20-PadC)") (class "Default")
      (node (ref "D20") (pin "C") (pinfunction "C_C") (pintype "passive"))
      (node (ref "Q6") (pin "G") (pinfunction "G_G") (pintype "passive"))
      (node (ref "R45") (pin "1") (pinfunction "1_1") (pintype "passive"))
    )
    (net (code "53") (name "Net-(IC1-BR)") (class "Default")
      (node (ref "IC1") (pin "8") (pinfunction "BR_8") (pintype "input"))
      (node (ref "R17") (pin "1") (pinfunction "1_1") (pintype "passive"))
      (node (ref "R8") (pin "2") (pinfunction "2_2") (pintype "passive"))
    )
    (net (code "54") (name "Net-(IC1-FB)") (class "Default")
      (node (ref "C23") (pin "2") (pinfunction "2_2") (pintype "passive"))
      (node (ref "C25") (pin "1") (pinfunction "1_1") (pintype "passive"))
      (node (ref "IC1") (pin "7") (pinfunction "FB_7") (pintype "input"))
      (node (ref "OK1") (pin "4") (pinfunction "COL_4") (pintype "passive"))
    )
    (net (code "55") (name "Net-(IC1-ZCD)") (class "Default")
      (node (ref "C24") (pin "1") (pinfunction "1_1") (pintype "passive"))
      (node (ref "IC1") (pin "6") (pinfunction "ZCD_6") (pintype "input"))
      (node (ref "R13") (pin "1") (pinfunction "1_1") (pintype "passive"))
      (node (ref "R14") (pin "1") (pinfunction "1_1") (pintype "passive"))
      (node (ref "R16") (pin "2") (pinfunction "2_2") (pintype "passive"))
    )
    (net (code "56") (name "Net-(IC2-DT)") (class "Default")
      (node (ref "IC2") (pin "6") (pinfunction "DT_6") (pintype "input"))
      (node (ref "R30") (pin "2") (pinfunction "2_2") (pintype "passive"))
    )
    (net (code "57") (name "Net-(IC2-VDDA)") (class "Default")
      (node (ref "C30") (pin "1") (pinfunction "1_1") (pintype "passive"))
      (node (ref "C31") (pin "1") (pinfunction "1_1") (pintype "passive"))
      (node (ref "C32") (pin "1") (pinfunction "1_1") (pintype "passive"))
      (node (ref "D10") (pin "1") (pinfunction "C_1") (pintype "passive"))
      (node (ref "D10") (pin "3") (pinfunction "C_3") (pintype "passive"))
      (node (ref "IC2") (pin "16") (pinfunction "VDDA_16") (pintype "power_in"))
    )
    (net (code "58") (name "Net-(IC2-VDDB)") (class "Default")
      (node (ref "C35") (pin "1") (pinfunction "1_1") (pintype "passive"))
      (node (ref "C36") (pin "1") (pinfunction "1_1") (pintype "passive"))
      (node (ref "C37") (pin "1") (pinfunction "1_1") (pintype "passive"))
      (node (ref "D13") (pin "C") (pinfunction "C_C") (pintype "passive"))
      (node (ref "IC2") (pin "11") (pinfunction "VDDB_11") (pintype "power_in"))
    )
    (net (code "59") (name "Net-(IC2-VIA)") (class "Default")
      (node (ref "IC2") (pin "1") (pinfunction "VIA_1") (pintype "input"))
      (node (ref "R25") (pin "1") (pinfunction "1_1") (pintype "passive"))
    )
    (net (code "60") (name "Net-(IC2-VIB)") (class "Default")
      (node (ref "IC2") (pin "2") (pinfunction "VIB_2") (pintype "input"))
      (node (ref "R27") (pin "1") (pinfunction "1_1") (pintype "passive"))
    )
    (net (code "61") (name "Net-(IC3-CS)") (class "Default")
      (node (ref "C47") (pin "2") (pinfunction "2_2") (pintype "passive"))
      (node (ref "IC3") (pin "12") (pinfunction "CS_12") (pintype "input"))
      (node (ref "R49") (pin "2") (pinfunction "2_2") (pintype "passive"))
    )
    (net (code "62") (name "Net-(IC3-RT{slash}SYNC)") (class "Default")
      (node (ref "IC3") (pin "15") (pinfunction "RT/SYNC_15") (pintype "input"))
      (node (ref "R48") (pin "1") (pinfunction "1_1") (pintype "passive"))
    )
    (net (code "63") (name "Net-(IC3-SS)") (class "Default")
      (node (ref "C42") (pin "2") (pinfunction "2_2") (pintype "passive"))
      (node (ref "IC3") (pin "13") (pinfunction "SS_13") (pintype "passive"))
    )
    (net (code "64") (name "Net-(IC3-TIME)") (class "Default")
      (node (ref "IC3") (pin "14") (pinfunction "TIME_14") (pintype "input"))
      (node (ref "R47") (pin "1") (pinfunction "1_1") (pintype "passive"))
    )
    (net (code "65") (name "Net-(IC3-UVLO)") (class "Default")
      (node (ref "IC3") (pin "16") (pinfunction "UVLO_16") (pintype "input"))
      (node (ref "R42") (pin "1") (pinfunction "1_1") (pintype "passive"))
      (node (ref "ZD5") (pin "C") (pinfunction "C_C") (pintype "passive"))
    )
    (net (code "66") (name "Net-(IC3-VCC)") (class "Default")
      (node (ref "C40") (pin "1") (pinfunction "1_1") (pintype "passive"))
      (node (ref "C41") (pin "1") (pinfunction "1_1") (pintype "passive"))
      (node (ref "IC3") (pin "1") (pinfunction "VIN_1") (pintype "input"))
      (node (ref "IC3") (pin "7") (pinfunction "VCC_7") (pintype "power_in"))
      (node (ref "R41") (pin "1") (pinfunction "1_1") (pintype "passive"))
    )
    (net (code "67") (name "Net-(IC4A-+IN)") (class "Default")
      (node (ref "IC4") (pin "3") (pinfunction "+IN_3") (pintype "input"))
      (node (ref "R54") (pin "1") (pinfunction "1_1") (pintype "passive"))
      (node (ref "X4") (pin "2") (pinfunction "1_2") (pintype "passive"))
    )
    (net (code "68") (name "Net-(IC4A--IN)") (class "Default")
      (node (ref "IC4") (pin "1") (pinfunction "OUT_1") (pintype "output"))
      (node (ref "IC4") (pin "2") (pinfunction "-IN_2") (pintype "input"))
      (node (ref "IC4") (pin "5") (pinfunction "+IN_5") (pintype "input"))
    )
    (net (code "69") (name "Net-(IC4B--IN)") (class "Default")
      (node (ref "IC4") (pin "6") (pinfunction "-IN_6") (pintype "input"))
      (node (ref "R51") (pin "1") (pinfunction "1_1") (pintype "passive"))
      (node (ref "R53") (pin "1") (pinfunction "1_1") (pintype "passive"))
    )
    (net (code "70") (name "Net-(IC4B-OUT)") (class "Default")
      (node (ref "IC4") (pin "7") (pinfunction "OUT_7") (pintype "output"))
      (node (ref "R46") (pin "2") (pinfunction "2_2") (pintype "passive"))
      (node (ref "R52") (pin "1") (pinfunction "1_1") (pintype "passive"))
    )
    (net (code "71") (name "Net-(IC5-GATE1)") (class "Default")
      (node (ref "D21") (pin "C") (pinfunction "C_C") (pintype "passive"))
      (node (ref "IC5") (pin "1") (pinfunction "GATE1_1") (pintype "output"))
      (node (ref "R59") (pin "2") (pinfunction "2_2") (pintype "passive"))
    )
    (net (code "72") (name "Net-(IC5-GATE2)") (class "Default")
      (node (ref "D22") (pin "C") (pinfunction "C_C") (pintype "passive"))
      (node (ref "IC5") (pin "8") (pinfunction "GATE2_8") (pintype "output"))
      (node (ref "R62") (pin "2") (pinfunction "2_2") (pintype "passive"))
    )
    (net (code "73") (name "Net-(IC5-MOT)") (class "Default")
      (node (ref "IC5") (pin "3") (pinfunction "MOT_3") (pintype "passive"))
      (node (ref "R61") (pin "1") (pinfunction "1_1") (pintype "passive"))
    )
    (net (code "74") (name "Net-(IC5-VCC)") (class "Default")
      (node (ref "C61") (pin "1") (pinfunction "1_1") (pintype "passive"))
      (node (ref "C62") (pin "1") (pinfunction "1_1") (pintype "passive"))
      (node (ref "IC5") (pin "2") (pinfunction "VCC_2") (pintype "power_in"))
      (node (ref "R60") (pin "2") (pinfunction "2_2") (pintype "passive"))
    )
    (net (code "75") (name "Net-(IC6A--IN)") (class "Default")
      (node (ref "C67") (pin "2") (pinfunction "2_2") (pintype "passive"))
      (node (ref "IC6") (pin "2") (pinfunction "-IN_2") (pintype "input"))
      (node (ref "R68") (pin "2") (pinfunction "2_2") (pintype "passive"))
      (node (ref "R69") (pin "1") (pinfunction "1_1") (pintype "passive"))
      (node (ref "R73") (pin "1") (pinfunction "1_1") (pintype "passive"))
    )
    (net (code "76") (name "Net-(IC6A-OUT)") (class "Default")
      (node (ref "C67") (pin "1") (pinfunction "1_1") (pintype "passive"))
      (node (ref "IC6") (pin "1") (pinfunction "OUT_1") (pintype "output"))
      (node (ref "R77") (pin "2") (pinfunction "2_2") (pintype "passive"))
    )
    (net (code "77") (name "Net-(IC6B--IN)") (class "Default")
      (node (ref "IC6") (pin "6") (pinfunction "-IN_6") (pintype "input"))
      (node (ref "R65") (pin "2") (pinfunction "2_2") (pintype "passive"))
      (node (ref "R67") (pin "1") (pinfunction "1_1") (pintype "passive"))
    )
    (net (code "78") (name "Net-(IC6B-OUT)") (class "Default")
      (node (ref "IC6") (pin "7") (pinfunction "OUT_7") (pintype "output"))
      (node (ref "R65") (pin "1") (pinfunction "1_1") (pintype "passive"))
      (node (ref "R69") (pin "2") (pinfunction "2_2") (pintype "passive"))
    )
    (net (code "79") (name "Net-(IC7A--IN1)") (class "Default")
      (node (ref "C68") (pin "2") (pinfunction "2_2") (pintype "passive"))
      (node (ref "IC7") (pin "2") (pinfunction "-IN1_2") (pintype "input"))
      (node (ref "R74") (pin "1") (pinfunction "1_1") (pintype "passive"))
      (node (ref "R75") (pin "1") (pinfunction "1_1") (pintype "passive"))
    )
    (net (code "80") (name "Net-(IC7A-OUT1)") (class "Default")
      (node (ref "C68") (pin "1") (pinfunction "1_1") (pintype "passive"))
      (node (ref "C69") (pin "1") (pinfunction "1_1") (pintype "passive"))
      (node (ref "IC7") (pin "1") (pinfunction "OUT1_1") (pintype "output"))
      (node (ref "OK3") (pin "2") (pinfunction "C_2") (pintype "passive"))
    )
    (net (code "81") (name "Net-(IC7B-+IN)") (class "Default")
      (node (ref "IC7") (pin "5") (pinfunction "+IN_5") (pintype "input"))
      (node (ref "JP3") (pin "COM") (pinfunction "COM_COM") (pintype "passive"))
    )
    (net (code "82") (name "Net-(IC7B--IN)") (class "Default")
      (node (ref "IC7") (pin "6") (pinfunction "-IN_6") (pintype "input"))
      (node (ref "IC7") (pin "7") (pinfunction "OUT_7") (pintype "output"))
      (node (ref "R73") (pin "2") (pinfunction "2_2") (pintype "passive"))
    )
    (net (code "83") (name "Net-(JP3-PadNO)") (class "Default")
      (node (ref "JP3") (pin "NO") (pinfunction "NO_NO") (pintype "passive"))
      (node (ref "P1") (pin "S") (pinfunction "S_S") (pintype "passive"))
    )
    (net (code "84") (name "Net-(L1B-1)") (class "Default")
      (node (ref "B1") (pin "AC1") (pinfunction "AC1_AC1") (pintype "passive"))
      (node (ref "C2") (pin "2") (pinfunction "2_2") (pintype "passive"))
      (node (ref "C4") (pin "2") (pinfunction "2_2") (pintype "passive"))
      (node (ref "L1") (pin "3") (pinfunction "1_3") (pintype "passive"))
      (node (ref "SAR2") (pin "2") (pinfunction "P$2_2") (pintype "bidirectional"))
    )
    (net (code "85") (name "Net-(LED1-PadA)") (class "Default")
      (node (ref "LED1") (pin "A") (pinfunction "A_A") (pintype "passive"))
      (node (ref "R11") (pin "2") (pinfunction "2_2") (pintype "passive"))
    )
    (net (code "86") (name "Net-(LED2-PadA)") (class "Default")
      (node (ref "LED2") (pin "A") (pinfunction "A_A") (pintype "passive"))
      (node (ref "R36") (pin "2") (pinfunction "2_2") (pintype "passive"))
    )
    (net (code "87") (name "Net-(OK1-A)") (class "Default")
      (node (ref "OK1") (pin "1") (pinfunction "A_1") (pintype "passive"))
      (node (ref "R15") (pin "2") (pinfunction "2_2") (pintype "passive"))
    )
    (net (code "88") (name "Net-(OK1-C)") (class "Default")
      (node (ref "OK1") (pin "2") (pinfunction "C_2") (pintype "passive"))
      (node (ref "R19") (pin "1") (pinfunction "1_1") (pintype "passive"))
      (node (ref "ZD3") (pin "C") (pinfunction "C_C") (pintype "passive"))
    )
    (net (code "89") (name "Net-(OK2-C)") (class "Default")
      (node (ref "OK2") (pin "2") (pinfunction "C_2") (pintype "passive"))
      (node (ref "R36") (pin "1") (pinfunction "1_1") (pintype "passive"))
    )
    (net (code "90") (name "Net-(OK3-A)") (class "Default")
      (node (ref "OK3") (pin "1") (pinfunction "A_1") (pintype "passive"))
      (node (ref "R70") (pin "1") (pinfunction "1_1") (pintype "passive"))
    )
    (net (code "91") (name "Net-(Q5-A)") (class "Default")
      (node (ref "D17") (pin "C") (pinfunction "C_C") (pintype "passive"))
      (node (ref "D18") (pin "C") (pinfunction "C_C") (pintype "passive"))
      (node (ref "Q5") (pin "3") (pinfunction "A_3") (pintype "passive"))
    )
    (net (code "92") (name "Net-(Q5-G)") (class "Default")
      (node (ref "Q5") (pin "2") (pinfunction "G_2") (pintype "passive"))
      (node (ref "R46") (pin "1") (pinfunction "1_1") (pintype "passive"))
    )
    (net (code "93") (name "Net-(R1-Pad2)") (class "Default")
      (node (ref "R1") (pin "2") (pinfunction "2_2") (pintype "passive"))
      (node (ref "R2") (pin "1") (pinfunction "1_1") (pintype "passive"))
    )
    (net (code "94") (name "Net-(R7-Pad2)") (class "Default")
      (node (ref "R7") (pin "2") (pinfunction "2_2") (pintype "passive"))
      (node (ref "R8") (pin "1") (pinfunction "1_1") (pintype "passive"))
    )
    (net (code "95") (name "Net-(R26-Pad1)") (class "Default")
      (node (ref "R26") (pin "1") (pinfunction "1_1") (pintype "passive"))
      (node (ref "R28") (pin "2") (pinfunction "2_2") (pintype "passive"))
    )
    (net (code "96") (name "Net-(R32-Pad2)") (class "Default")
      (node (ref "R32") (pin "2") (pinfunction "2_2") (pintype "passive"))
      (node (ref "R40") (pin "1") (pinfunction "1_1") (pintype "passive"))
    )
    (net (code "97") (name "Net-(R66-Pad1)") (class "Default")
      (node (ref "R66") (pin "1") (pinfunction "1_1") (pintype "passive"))
      (node (ref "R71") (pin "2") (pinfunction "2_2") (pintype "passive"))
    )
    (net (code "98") (name "Net-(R71-Pad1)") (class "Default")
      (node (ref "R71") (pin "1") (pinfunction "1_1") (pintype "passive"))
      (node (ref "R75") (pin "2") (pinfunction "2_2") (pintype "passive"))
      (node (ref "R76") (pin "2") (pinfunction "2_2") (pintype "passive"))
    )
    (net (code "99") (name "Net-(SAR1-P$2)") (class "Default")
      (node (ref "B1") (pin "AC2") (pinfunction "AC2_AC2") (pintype "passive"))
      (node (ref "C2") (pin "1") (pinfunction "1_1") (pintype "passive"))
      (node (ref "C5") (pin "2") (pinfunction "2_2") (pintype "passive"))
      (node (ref "L1") (pin "1") (pinfunction "1_1") (pintype "passive"))
      (node (ref "SAR1") (pin "2") (pinfunction "P$2_2") (pintype "bidirectional"))
    )
    (net (code "100") (name "Net-(TR1-P2_DOT)") (class "Default")
      (node (ref "D3") (pin "A") (pinfunction "A_A") (pintype "passive"))
      (node (ref "IC1") (pin "13") (pinfunction "DRAIN_13") (pintype "output"))
      (node (ref "IC1") (pin "14") (pinfunction "DRAIN_14") (pintype "output"))
      (node (ref "IC1") (pin "15") (pinfunction "DRAIN_15") (pintype "output"))
      (node (ref "IC1") (pin "16") (pinfunction "DRAIN_16") (pintype "output"))
      (node (ref "TR1") (pin "4") (pinfunction "P2_DOT_4") (pintype "passive"))
    )
    (net (code "101") (name "Net-(TR1-S2)") (class "Default")
      (node (ref "C16") (pin "2") (pinfunction "2_2") (pintype "passive"))
      (node (ref "D4") (pin "C") (pinfunction "C_C") (pintype "passive"))
      (node (ref "TR1") (pin "8") (pinfunction "S2_8") (pintype "passive"))
    )
    (net (code "102") (name "Net-(TR1-S3_DOT)") (class "Default")
      (node (ref "C9") (pin "2") (pinfunction "2_2") (pintype "passive"))
      (node (ref "D2") (pin "A") (pinfunction "A_A") (pintype "passive"))
      (node (ref "TR1") (pin "15") (pinfunction "S3_DOT_15") (pintype "passive"))
    )
    (net (code "103") (name "Net-(TR2-P)") (class "Default")
      (node (ref "Q2") (pin "D") (pinfunction "D_D") (pintype "passive"))
      (node (ref "TR2") (pin "7") (pinfunction "P_7") (pintype "passive"))
    )
    (net (code "104") (name "Net-(TR2-S_DOT)") (class "Default")
      (node (ref "D9") (pin "A") (pinfunction "A_A") (pintype "passive"))
      (node (ref "R20") (pin "1") (pinfunction "1_1") (pintype "passive"))
      (node (ref "TR2") (pin "1") (pinfunction "S_DOT_1") (pintype "passive"))
    )
    (net (code "105") (name "PE") (class "Default")
      (node (ref "C4") (pin "1") (pinfunction "1_1") (pintype "passive"))
      (node (ref "C4A") (pin "1") (pinfunction "1_1") (pintype "passive"))
      (node (ref "C5") (pin "1") (pinfunction "1_1") (pintype "passive"))
      (node (ref "C5A") (pin "1") (pinfunction "1_1") (pintype "passive"))
      (node (ref "JP2") (pin "NC") (pinfunction "NC_NC") (pintype "passive"))
      (node (ref "X1") (pin "3") (pinfunction "1_3") (pintype "passive"))
      (node (ref "X3") (pin "8") (pinfunction "S_8") (pintype "passive"))
    )
    (net (code "106") (name "POUT+") (class "Default")
      (node (ref "C51") (pin "+") (pinfunction "+_+") (pintype "passive"))
      (node (ref "C52") (pin "+") (pinfunction "+_+") (pintype "passive"))
      (node (ref "C53") (pin "+") (pinfunction "+_+") (pintype "passive"))
      (node (ref "C54") (pin "1") (pinfunction "1_1") (pintype "passive"))
      (node (ref "L7") (pin "1") (pinfunction "1_1") (pintype "passive"))
      (node (ref "R55") (pin "1") (pinfunction "1_1") (pintype "passive"))
      (node (ref "R66") (pin "2") (pinfunction "2_2") (pintype "passive"))
      (node (ref "SH2") (pin "P$2") (pinfunction "GND_B_P$2") (pintype "bidirectional"))
      (node (ref "SH3") (pin "P$1") (pinfunction "GND_A_P$1") (pintype "bidirectional"))
    )
    (net (code "107") (name "PREG_OUT+") (class "Default")
      (node (ref "C55") (pin "1") (pinfunction "1_1") (pintype "passive"))
      (node (ref "C56") (pin "1") (pinfunction "1_1") (pintype "passive"))
      (node (ref "C57") (pin "1") (pinfunction "1_1") (pintype "passive"))
      (node (ref "C58") (pin "1") (pinfunction "1_1") (pintype "passive"))
      (node (ref "JP1") (pin "NC") (pinfunction "NC_NC") (pintype "passive"))
      (node (ref "L7") (pin "2") (pinfunction "2_2") (pintype "passive"))
      (node (ref "R55") (pin "2") (pinfunction "2_2") (pintype "passive"))
      (node (ref "R56") (pin "2") (pinfunction "2_2") (pintype "passive"))
      (node (ref "TP6") (pin "TIP") (pinfunction "TIP_TIP") (pintype "bidirectional"))
      (node (ref "X5") (pin "1") (pinfunction "1_1") (pintype "passive"))
      (node (ref "ZD6") (pin "C") (pinfunction "C_C") (pintype "passive"))
    )
    (net (code "108") (name "PULL") (class "Default")
      (node (ref "D20") (pin "A") (pinfunction "A_A") (pintype "passive"))
      (node (ref "IC3") (pin "9") (pinfunction "PULL_9") (pintype "output"))
      (node (ref "R45") (pin "2") (pinfunction "2_2") (pintype "passive"))
    )
    (net (code "109") (name "PUSH") (class "Default")
      (node (ref "D19") (pin "A") (pinfunction "A_A") (pintype "passive"))
      (node (ref "IC3") (pin "8") (pinfunction "PUSH_8") (pintype "output"))
      (node (ref "R44") (pin "2") (pinfunction "2_2") (pintype "passive"))
    )
    (net (code "110") (name "REF") (class "Default")
      (node (ref "C34") (pin "2") (pinfunction "2_2") (pintype "passive"))
      (node (ref "IC2") (pin "3") (pinfunction "VDDI_3") (pintype "power_in"))
      (node (ref "IC2") (pin "8") (pinfunction "VDDI_8") (pintype "power_in"))
      (node (ref "R33") (pin "2") (pinfunction "2_2") (pintype "passive"))
      (node (ref "ZD4") (pin "C") (pinfunction "C_C") (pintype "passive"))
    )
    (net (code "111") (name "S1_DOT_OUT") (class "Default")
      (node (ref "IC5") (pin "4") (pinfunction "VD1_4") (pintype "passive"))
      (node (ref "Q7") (pin "3") (pinfunction "D_3") (pintype "passive"))
      (node (ref "R57") (pin "1") (pinfunction "1_1") (pintype "passive"))
      (node (ref "R58") (pin "1") (pinfunction "1_1") (pintype "passive"))
      (node (ref "TR3") (pin "S1_DOT") (pinfunction "S1_DOT_S1_DOT") (pintype "passive"))
    )
    (net (code "112") (name "S1_OUT") (class "Default")
      (node (ref "SH2") (pin "P$1") (pinfunction "GND_A_P$1") (pintype "bidirectional"))
      (node (ref "TR3") (pin "S1") (pinfunction "S1_S1") (pintype "passive"))
    )
    (net (code "113") (name "S2_DOT_OUT") (class "Default")
      (node (ref "SH3") (pin "P$2") (pinfunction "GND_B_P$2") (pintype "bidirectional"))
      (node (ref "TR3") (pin "S2_DOT") (pinfunction "S2_DOT_S2_DOT") (pintype "passive"))
    )
    (net (code "114") (name "S2_OUT") (class "Default")
      (node (ref "IC5") (pin "5") (pinfunction "VD2_5") (pintype "passive"))
      (node (ref "Q8") (pin "3") (pinfunction "D_3") (pintype "passive"))
      (node (ref "R63") (pin "1") (pinfunction "1_1") (pintype "passive"))
      (node (ref "R64") (pin "1") (pinfunction "1_1") (pintype "passive"))
      (node (ref "TR3") (pin "S2") (pinfunction "S2_S2") (pintype "passive"))
    )
    (net (code "115") (name "SR_OUT1") (class "Default")
      (node (ref "D21") (pin "A") (pinfunction "A_A") (pintype "passive"))
      (node (ref "Q7") (pin "1") (pinfunction "G_1") (pintype "passive"))
      (node (ref "R59") (pin "1") (pinfunction "1_1") (pintype "passive"))
    )
    (net (code "116") (name "SR_OUT2") (class "Default")
      (node (ref "D22") (pin "A") (pinfunction "A_A") (pintype "passive"))
      (node (ref "Q8") (pin "1") (pinfunction "G_1") (pintype "passive"))
      (node (ref "R62") (pin "1") (pinfunction "1_1") (pintype "passive"))
    )
    (net (code "117") (name "U_MON") (class "Default")
      (node (ref "JP3") (pin "NC") (pinfunction "NC_NC") (pintype "passive"))
      (node (ref "X3") (pin "1") (pinfunction "S_1") (pintype "passive"))
    )
    (net (code "118") (name "V+") (class "Default")
      (node (ref "C22") (pin "1") (pinfunction "1_1") (pintype "passive"))
      (node (ref "C63") (pin "1") (pinfunction "1_1") (pintype "passive"))
      (node (ref "C66") (pin "1") (pinfunction "1_1") (pintype "passive"))
      (node (ref "IC6") (pin "8") (pinfunction "V+_8") (pintype "power_in"))
      (node (ref "IC7") (pin "8") (pinfunction "VCC+_8") (pintype "power_in"))
      (node (ref "L4") (pin "2") (pinfunction "2_2") (pintype "passive"))
      (node (ref "R11") (pin "1") (pinfunction "1_1") (pintype "passive"))
      (node (ref "R12") (pin "1") (pinfunction "1_1") (pintype "passive"))
      (node (ref "R19") (pin "2") (pinfunction "2_2") (pintype "passive"))
      (node (ref "R60") (pin "1") (pinfunction "1_1") (pintype "passive"))
      (node (ref "R70") (pin "2") (pinfunction "2_2") (pintype "passive"))
      (node (ref "R72") (pin "2") (pinfunction "2_2") (pintype "passive"))
      (node (ref "X3") (pin "5") (pinfunction "S_5") (pintype "passive"))
    )
    (net (code "119") (name "V-") (class "Default")
      (node (ref "C15") (pin "2") (pinfunction "2_2") (pintype "passive"))
      (node (ref "C65") (pin "1") (pinfunction "1_1") (pintype "passive"))
      (node (ref "IC6") (pin "4") (pinfunction "V-_4") (pintype "power_in"))
      (node (ref "L3") (pin "2") (pinfunction "2_2") (pintype "passive"))
      (node (ref "X3") (pin "7") (pinfunction "S_7") (pintype "passive"))
    )
    (net (code "120") (name "~{FAULT}") (class "Default")
      (node (ref "OK2") (pin "4") (pinfunction "COL_4") (pintype "passive"))
      (node (ref "R12") (pin "2") (pinfunction "2_2") (pintype "passive"))
      (node (ref "X3") (pin "4") (pinfunction "S_4") (pintype "passive"))
    )
  )
)
